# ARM_board.net
KiCad netlist of a schematic drawn in EAGLE
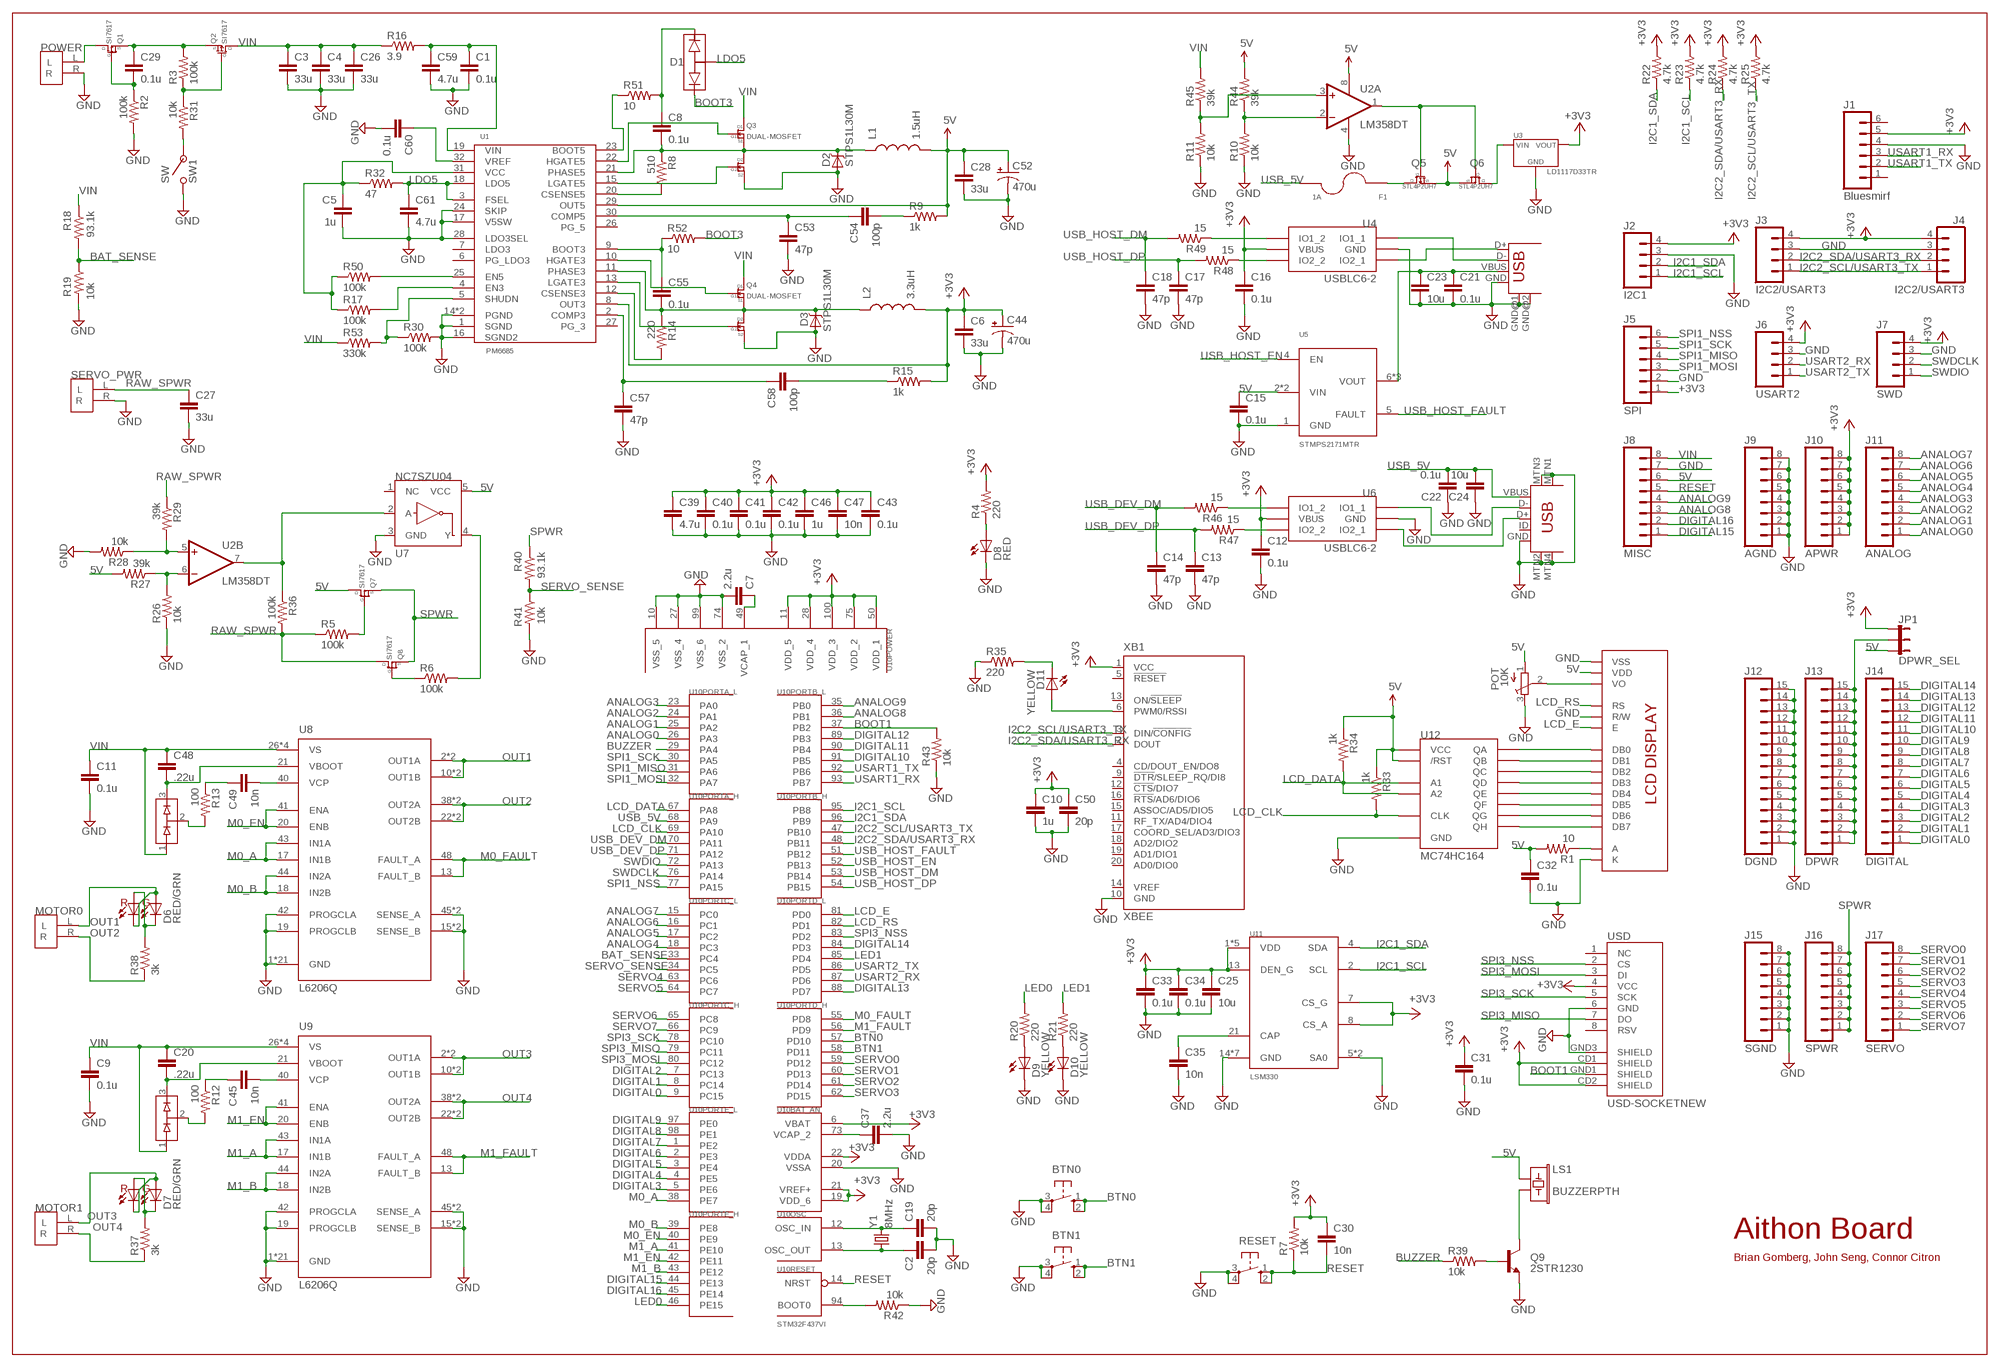
[diagram p0: schematic, sheet 1]

(export (version "E")
  (design (tool "Eeschema 10.0.6"))
  (components
    (comp (ref "BTN0")
      (value "10-XX")
      (footprint "eagle-import:B3F-10XX")
      (fields (field (name "MPN") "B3F-1000"))
      (libsource (lib "eagle-import") (part "10-XX"))
    )
    (comp (ref "BTN1")
      (value "10-XX")
      (footprint "eagle-import:B3F-10XX")
      (fields (field (name "MPN") "B3F-1000"))
      (libsource (lib "eagle-import") (part "10-XX"))
    )
    (comp (ref "C1")
      (value "0.1u")
      (footprint "eagle-import:0402-CAP")
      (libsource (lib "eagle-import") (part "CAP0402-CAP"))
    )
    (comp (ref "C2")
      (value "20p")
      (footprint "eagle-import:0402-CAP")
      (libsource (lib "eagle-import") (part "CAP0402-CAP"))
    )
    (comp (ref "C3")
      (value "33u")
      (footprint "eagle-import:1206")
      (libsource (lib "eagle-import") (part "CAP1206"))
    )
    (comp (ref "C4")
      (value "33u")
      (footprint "eagle-import:1206")
      (libsource (lib "eagle-import") (part "CAP1206"))
    )
    (comp (ref "C5")
      (value "1u")
      (footprint "eagle-import:0402-CAP")
      (libsource (lib "eagle-import") (part "CAP0402-CAP"))
    )
    (comp (ref "C6")
      (value "33u")
      (footprint "eagle-import:0805")
      (libsource (lib "eagle-import") (part "CAP0805"))
    )
    (comp (ref "C7")
      (value "2.2u")
      (footprint "eagle-import:0402-CAP")
      (libsource (lib "eagle-import") (part "CAP0402-CAP"))
    )
    (comp (ref "C8")
      (value "0.1u")
      (footprint "eagle-import:0402-CAP")
      (libsource (lib "eagle-import") (part "CAP0402-CAP"))
    )
    (comp (ref "C9")
      (value "0.1u")
      (footprint "eagle-import:0402-CAP")
      (libsource (lib "eagle-import") (part "CAP0402-CAP"))
    )
    (comp (ref "C10")
      (value "1u")
      (footprint "eagle-import:0402-CAP")
      (libsource (lib "eagle-import") (part "CAP0402-CAP"))
    )
    (comp (ref "C11")
      (value "0.1u")
      (footprint "eagle-import:0402-CAP")
      (libsource (lib "eagle-import") (part "CAP0402-CAP"))
    )
    (comp (ref "C12")
      (value "0.1u")
      (footprint "eagle-import:0402-CAP")
      (libsource (lib "eagle-import") (part "CAP0402-CAP"))
    )
    (comp (ref "C13")
      (value "47p")
      (footprint "eagle-import:0402-CAP")
      (libsource (lib "eagle-import") (part "CAP0402-CAP"))
    )
    (comp (ref "C14")
      (value "47p")
      (footprint "eagle-import:0402-CAP")
      (libsource (lib "eagle-import") (part "CAP0402-CAP"))
    )
    (comp (ref "C15")
      (value "0.1u")
      (footprint "eagle-import:0402-CAP")
      (libsource (lib "eagle-import") (part "CAP0402-CAP"))
    )
    (comp (ref "C16")
      (value "0.1u")
      (footprint "eagle-import:0402-CAP")
      (libsource (lib "eagle-import") (part "CAP0402-CAP"))
    )
    (comp (ref "C17")
      (value "47p")
      (footprint "eagle-import:0402-CAP")
      (libsource (lib "eagle-import") (part "CAP0402-CAP"))
    )
    (comp (ref "C18")
      (value "47p")
      (footprint "eagle-import:0402-CAP")
      (libsource (lib "eagle-import") (part "CAP0402-CAP"))
    )
    (comp (ref "C19")
      (value "20p")
      (footprint "eagle-import:0402-CAP")
      (libsource (lib "eagle-import") (part "CAP0402-CAP"))
    )
    (comp (ref "C20")
      (value ".22u")
      (footprint "eagle-import:0402-CAP")
      (libsource (lib "eagle-import") (part "CAP0402-CAP"))
    )
    (comp (ref "C21")
      (value "0.1u")
      (footprint "eagle-import:0402-CAP")
      (libsource (lib "eagle-import") (part "CAP0402-CAP"))
    )
    (comp (ref "C22")
      (value "0.1u")
      (footprint "eagle-import:0402-CAP")
      (libsource (lib "eagle-import") (part "CAP0402-CAP"))
    )
    (comp (ref "C23")
      (value "10u")
      (footprint "eagle-import:0603-CAP")
      (libsource (lib "eagle-import") (part "CAP0603-CAP"))
    )
    (comp (ref "C24")
      (value "10u")
      (footprint "eagle-import:0603-CAP")
      (libsource (lib "eagle-import") (part "CAP0603-CAP"))
    )
    (comp (ref "C25")
      (value "10u")
      (footprint "eagle-import:0603-CAP")
      (libsource (lib "eagle-import") (part "CAP0603-CAP"))
    )
    (comp (ref "C26")
      (value "33u")
      (footprint "eagle-import:1206")
      (libsource (lib "eagle-import") (part "CAP1206"))
    )
    (comp (ref "C27")
      (value "33u")
      (footprint "eagle-import:1206")
      (libsource (lib "eagle-import") (part "CAP1206"))
    )
    (comp (ref "C28")
      (value "33u")
      (footprint "eagle-import:0805")
      (libsource (lib "eagle-import") (part "CAP0805"))
    )
    (comp (ref "C29")
      (value "0.1u")
      (footprint "eagle-import:0402-CAP")
      (libsource (lib "eagle-import") (part "CAP0402-CAP"))
    )
    (comp (ref "C30")
      (value "10n")
      (footprint "eagle-import:0402-CAP")
      (libsource (lib "eagle-import") (part "CAP0402-CAP"))
    )
    (comp (ref "C31")
      (value "0.1u")
      (footprint "eagle-import:0402-CAP")
      (libsource (lib "eagle-import") (part "CAP0402-CAP"))
    )
    (comp (ref "C32")
      (value "0.1u")
      (footprint "eagle-import:0402-CAP")
      (libsource (lib "eagle-import") (part "CAP0402-CAP"))
    )
    (comp (ref "C33")
      (value "0.1u")
      (footprint "eagle-import:0402-CAP")
      (libsource (lib "eagle-import") (part "CAP0402-CAP"))
    )
    (comp (ref "C34")
      (value "0.1u")
      (footprint "eagle-import:0402-CAP")
      (libsource (lib "eagle-import") (part "CAP0402-CAP"))
    )
    (comp (ref "C35")
      (value "10n")
      (footprint "eagle-import:0402-CAP")
      (libsource (lib "eagle-import") (part "CAP0402-CAP"))
    )
    (comp (ref "C37")
      (value "2.2u")
      (footprint "eagle-import:0402-CAP")
      (libsource (lib "eagle-import") (part "CAP0402-CAP"))
    )
    (comp (ref "C39")
      (value "4.7u")
      (footprint "eagle-import:0603-CAP")
      (libsource (lib "eagle-import") (part "CAP0603-CAP"))
    )
    (comp (ref "C40")
      (value "0.1u")
      (footprint "eagle-import:0402-CAP")
      (libsource (lib "eagle-import") (part "CAP0402-CAP"))
    )
    (comp (ref "C41")
      (value "0.1u")
      (footprint "eagle-import:0402-CAP")
      (libsource (lib "eagle-import") (part "CAP0402-CAP"))
    )
    (comp (ref "C42")
      (value "0.1u")
      (footprint "eagle-import:0402-CAP")
      (libsource (lib "eagle-import") (part "CAP0402-CAP"))
    )
    (comp (ref "C43")
      (value "0.1u")
      (footprint "eagle-import:0402-CAP")
      (libsource (lib "eagle-import") (part "CAP0402-CAP"))
    )
    (comp (ref "C44")
      (value "470u")
      (footprint "eagle-import:PANASONIC_D")
      (libsource (lib "eagle-import") (part "CAP_POLD"))
    )
    (comp (ref "C45")
      (value "10n")
      (footprint "eagle-import:0402-CAP")
      (libsource (lib "eagle-import") (part "CAP0402-CAP"))
    )
    (comp (ref "C46")
      (value "1u")
      (footprint "eagle-import:0402-CAP")
      (libsource (lib "eagle-import") (part "CAP0402-CAP"))
    )
    (comp (ref "C47")
      (value "10n")
      (footprint "eagle-import:0402-CAP")
      (libsource (lib "eagle-import") (part "CAP0402-CAP"))
    )
    (comp (ref "C48")
      (value ".22u")
      (footprint "eagle-import:0402-CAP")
      (libsource (lib "eagle-import") (part "CAP0402-CAP"))
    )
    (comp (ref "C49")
      (value "10n")
      (footprint "eagle-import:0402-CAP")
      (libsource (lib "eagle-import") (part "CAP0402-CAP"))
    )
    (comp (ref "C50")
      (value "20p")
      (footprint "eagle-import:0402-CAP")
      (libsource (lib "eagle-import") (part "CAP0402-CAP"))
    )
    (comp (ref "C52")
      (value "470u")
      (footprint "eagle-import:PANASONIC_D")
      (libsource (lib "eagle-import") (part "CAP_POLD"))
    )
    (comp (ref "C53")
      (value "47p")
      (footprint "eagle-import:0402-CAP")
      (libsource (lib "eagle-import") (part "CAP0402-CAP"))
    )
    (comp (ref "C54")
      (value "100p")
      (footprint "eagle-import:0402-CAP")
      (libsource (lib "eagle-import") (part "CAP0402-CAP"))
    )
    (comp (ref "C55")
      (value "0.1u")
      (footprint "eagle-import:0402-CAP")
      (libsource (lib "eagle-import") (part "CAP0402-CAP"))
    )
    (comp (ref "C57")
      (value "47p")
      (footprint "eagle-import:0402-CAP")
      (libsource (lib "eagle-import") (part "CAP0402-CAP"))
    )
    (comp (ref "C58")
      (value "100p")
      (footprint "eagle-import:0402-CAP")
      (libsource (lib "eagle-import") (part "CAP0402-CAP"))
    )
    (comp (ref "C59")
      (value "4.7u")
      (footprint "eagle-import:0603-CAP")
      (libsource (lib "eagle-import") (part "CAP0603-CAP"))
    )
    (comp (ref "C60")
      (value "0.1u")
      (footprint "eagle-import:0402-CAP")
      (libsource (lib "eagle-import") (part "CAP0402-CAP"))
    )
    (comp (ref "C61")
      (value "4.7u")
      (footprint "eagle-import:0603-CAP")
      (libsource (lib "eagle-import") (part "CAP0603-CAP"))
    )
    (comp (ref "D1")
      (value "BAS70-06FILM")
      (footprint "eagle-import:SOT-23")
      (libsource (lib "eagle-import") (part "SOD-23"))
    )
    (comp (ref "D2")
      (value "STPS1L30M")
      (footprint "eagle-import:STPS1L30M")
      (libsource (lib "eagle-import") (part "DIODE-SCHOTTKYA"))
    )
    (comp (ref "D3")
      (value "STPS1L30M")
      (footprint "eagle-import:STPS1L30M")
      (libsource (lib "eagle-import") (part "DIODE-SCHOTTKYA"))
    )
    (comp (ref "D4")
      (value "BAS70-05FILM")
      (footprint "eagle-import:SOT-23")
      (libsource (lib "eagle-import") (part "BAV99"))
    )
    (comp (ref "D5")
      (value "BAV99")
      (footprint "eagle-import:SOT-23")
      (libsource (lib "eagle-import") (part "BAV99"))
    )
    (comp (ref "D6")
      (value "RED/GRN")
      (footprint "eagle-import:LED-0606")
      (libsource (lib "eagle-import") (part "LED_BICOLOR"))
    )
    (comp (ref "D7")
      (value "RED/GRN")
      (footprint "eagle-import:LED-0606")
      (libsource (lib "eagle-import") (part "LED_BICOLOR"))
    )
    (comp (ref "D8")
      (value "RED")
      (footprint "eagle-import:CHIP-LED0603")
      (libsource (lib "eagle-import") (part "LEDCHIP-LED0603"))
    )
    (comp (ref "D9")
      (value "YELLOW")
      (footprint "eagle-import:CHIP-LED0603")
      (libsource (lib "eagle-import") (part "LEDCHIP-LED0603"))
    )
    (comp (ref "D10")
      (value "YELLOW")
      (footprint "eagle-import:CHIP-LED0603")
      (libsource (lib "eagle-import") (part "LEDCHIP-LED0603"))
    )
    (comp (ref "D11")
      (value "YELLOW")
      (footprint "eagle-import:CHIP-LED0603")
      (libsource (lib "eagle-import") (part "LEDCHIP-LED0603"))
    )
    (comp (ref "F1")
      (value "1A")
      (footprint "eagle-import:1206")
      (libsource (lib "eagle-import") (part "POLYFUSE"))
    )
    (comp (ref "J1")
      (value "Bluesmirf")
      (footprint "eagle-import:1X06")
      (libsource (lib "eagle-import") (part "M06SIP"))
    )
    (comp (ref "J2")
      (value "I2C1")
      (footprint "eagle-import:1X04")
      (libsource (lib "eagle-import") (part "M04PTH"))
    )
    (comp (ref "J3")
      (value "I2C2/USART3")
      (footprint "eagle-import:1X04")
      (libsource (lib "eagle-import") (part "M04PTH"))
    )
    (comp (ref "J4")
      (value "I2C2/USART3")
      (footprint "eagle-import:1X04")
      (libsource (lib "eagle-import") (part "M04PTH"))
    )
    (comp (ref "J5")
      (value "SPI")
      (footprint "eagle-import:1X06")
      (libsource (lib "eagle-import") (part "M06SIP"))
    )
    (comp (ref "J6")
      (value "USART2")
      (footprint "eagle-import:1X04")
      (libsource (lib "eagle-import") (part "M04PTH"))
    )
    (comp (ref "J7")
      (value "SWD")
      (footprint "eagle-import:1X04")
      (libsource (lib "eagle-import") (part "M04PTH"))
    )
    (comp (ref "J8")
      (value "MISC")
      (footprint "eagle-import:1X08")
      (libsource (lib "eagle-import") (part "M081X08"))
    )
    (comp (ref "J9")
      (value "AGND")
      (footprint "eagle-import:1X08")
      (libsource (lib "eagle-import") (part "M081X08"))
    )
    (comp (ref "J10")
      (value "APWR")
      (footprint "eagle-import:1X08")
      (libsource (lib "eagle-import") (part "M081X08"))
    )
    (comp (ref "J11")
      (value "ANALOG")
      (footprint "eagle-import:1X08")
      (libsource (lib "eagle-import") (part "M081X08"))
    )
    (comp (ref "J12")
      (value "DGND")
      (footprint "eagle-import:1X15")
      (libsource (lib "eagle-import") (part "M15"))
    )
    (comp (ref "J13")
      (value "DPWR")
      (footprint "eagle-import:1X15")
      (libsource (lib "eagle-import") (part "M15"))
    )
    (comp (ref "J14")
      (value "DIGITAL")
      (footprint "eagle-import:1X15")
      (libsource (lib "eagle-import") (part "M15"))
    )
    (comp (ref "J15")
      (value "SGND")
      (footprint "eagle-import:1X08")
      (libsource (lib "eagle-import") (part "M081X08"))
    )
    (comp (ref "J16")
      (value "SPWR")
      (footprint "eagle-import:1X08")
      (libsource (lib "eagle-import") (part "M081X08"))
    )
    (comp (ref "J17")
      (value "SERVO")
      (footprint "eagle-import:1X08")
      (libsource (lib "eagle-import") (part "M081X08"))
    )
    (comp (ref "JP1")
      (value "DPWR_SEL")
      (footprint "eagle-import:1X03")
      (libsource (lib "eagle-import") (part "JUMPER-3PTH"))
    )
    (comp (ref "L1")
      (value "1.5uH")
      (footprint "eagle-import:INDUCTOR-LMIP707")
      (libsource (lib "eagle-import") (part "INDUCTOR2"))
    )
    (comp (ref "L2")
      (value "3.3uH")
      (footprint "eagle-import:INDUCTOR-0520CDMCDS")
      (libsource (lib "eagle-import") (part "INDUCTOR3"))
    )
    (comp (ref "LCD")
      (value "LCD_DISPLAY")
      (footprint "eagle-import:LCD")
      (libsource (lib "eagle-import") (part "LCD_DISPLAY"))
    )
    (comp (ref "LS1")
      (value "BUZZERPTH")
      (footprint "eagle-import:BUZZER-12MM")
      (libsource (lib "eagle-import") (part "BUZZERPTH"))
    )
    (comp (ref "MOTOR0")
      (value "2POS_TERMINAL")
      (footprint "eagle-import:2POS_TERMINAL")
      (libsource (lib "eagle-import") (part "2POS_TERMINAL"))
    )
    (comp (ref "MOTOR1")
      (value "2POS_TERMINAL")
      (footprint "eagle-import:2POS_TERMINAL")
      (libsource (lib "eagle-import") (part "2POS_TERMINAL"))
    )
    (comp (ref "POT")
      (value "10K")
      (footprint "eagle-import:POT")
      (libsource (lib "eagle-import") (part "POT"))
    )
    (comp (ref "POWER")
      (value "2POS_TERMINAL")
      (footprint "eagle-import:2POS_TERMINAL")
      (libsource (lib "eagle-import") (part "2POS_TERMINAL"))
    )
    (comp (ref "Q1")
      (value "SI7617")
      (footprint "eagle-import:POWERPAK1212-8")
      (libsource (lib "eagle-import") (part "SI7617"))
    )
    (comp (ref "Q2")
      (value "SI7617")
      (footprint "eagle-import:POWERPAK1212-8")
      (libsource (lib "eagle-import") (part "SI7617"))
    )
    (comp (ref "Q3")
      (value "DUAL-MOSFET")
      (footprint "eagle-import:DUAL-MOSFET-STL60N32N3LL")
      (libsource (lib "eagle-import") (part "DUAL-MOSFET"))
    )
    (comp (ref "Q4")
      (value "DUAL-MOSFET")
      (footprint "eagle-import:DUAL-MOSFET-STL60N32N3LL")
      (libsource (lib "eagle-import") (part "DUAL-MOSFET"))
    )
    (comp (ref "Q5")
      (value "STL4P2UH7")
      (footprint "eagle-import:POWERFLAT")
      (libsource (lib "eagle-import") (part "STL4P2UH7"))
    )
    (comp (ref "Q6")
      (value "STL4P2UH7")
      (footprint "eagle-import:POWERFLAT")
      (libsource (lib "eagle-import") (part "STL4P2UH7"))
    )
    (comp (ref "Q7")
      (value "SI7617")
      (footprint "eagle-import:POWERPAK1212-8")
      (libsource (lib "eagle-import") (part "SI7617"))
    )
    (comp (ref "Q8")
      (value "SI7617")
      (footprint "eagle-import:POWERPAK1212-8")
      (libsource (lib "eagle-import") (part "SI7617"))
    )
    (comp (ref "Q9")
      (value "2STR1230")
      (footprint "eagle-import:SOT23-3")
      (libsource (lib "eagle-import") (part "TRANSISTOR_NPNSOT23-3"))
    )
    (comp (ref "R1")
      (value "10")
      (footprint "eagle-import:0402-RES")
      (libsource (lib "eagle-import") (part "RESISTOR0402-RES"))
    )
    (comp (ref "R2")
      (value "100k")
      (footprint "eagle-import:0402-RES")
      (libsource (lib "eagle-import") (part "RESISTOR0402-RES"))
    )
    (comp (ref "R3")
      (value "100k")
      (footprint "eagle-import:0402-RES")
      (libsource (lib "eagle-import") (part "RESISTOR0402-RES"))
    )
    (comp (ref "R4")
      (value "220")
      (footprint "eagle-import:0402-RES")
      (libsource (lib "eagle-import") (part "RESISTOR0402-RES"))
    )
    (comp (ref "R5")
      (value "100k")
      (footprint "eagle-import:0402-RES")
      (libsource (lib "eagle-import") (part "RESISTOR0402-RES"))
    )
    (comp (ref "R6")
      (value "100k")
      (footprint "eagle-import:0402-RES")
      (libsource (lib "eagle-import") (part "RESISTOR0402-RES"))
    )
    (comp (ref "R7")
      (value "10k")
      (footprint "eagle-import:0402-RES")
      (libsource (lib "eagle-import") (part "RESISTOR0402-RES"))
    )
    (comp (ref "R8")
      (value "510")
      (footprint "eagle-import:0402-RES")
      (libsource (lib "eagle-import") (part "RESISTOR0402-RES"))
    )
    (comp (ref "R9")
      (value "1k")
      (footprint "eagle-import:0402-RES")
      (libsource (lib "eagle-import") (part "RESISTOR0402-RES"))
    )
    (comp (ref "R10")
      (value "10k")
      (footprint "eagle-import:0402-RES")
      (libsource (lib "eagle-import") (part "RESISTOR0402-RES"))
    )
    (comp (ref "R11")
      (value "10k")
      (footprint "eagle-import:0402-RES")
      (libsource (lib "eagle-import") (part "RESISTOR0402-RES"))
    )
    (comp (ref "R12")
      (value "100")
      (footprint "eagle-import:0402-RES")
      (libsource (lib "eagle-import") (part "RESISTOR0402-RES"))
    )
    (comp (ref "R13")
      (value "100")
      (footprint "eagle-import:0402-RES")
      (libsource (lib "eagle-import") (part "RESISTOR0402-RES"))
    )
    (comp (ref "R14")
      (value "220")
      (footprint "eagle-import:0402-RES")
      (libsource (lib "eagle-import") (part "RESISTOR0402-RES"))
    )
    (comp (ref "R15")
      (value "1k")
      (footprint "eagle-import:0402-RES")
      (libsource (lib "eagle-import") (part "RESISTOR0402-RES"))
    )
    (comp (ref "R16")
      (value "3.9")
      (footprint "eagle-import:0402-RES")
      (libsource (lib "eagle-import") (part "RESISTOR0402-RES"))
    )
    (comp (ref "R17")
      (value "100k")
      (footprint "eagle-import:0402-RES")
      (libsource (lib "eagle-import") (part "RESISTOR0402-RES"))
    )
    (comp (ref "R18")
      (value "93.1k")
      (footprint "eagle-import:0402-RES")
      (libsource (lib "eagle-import") (part "RESISTOR0402-RES"))
    )
    (comp (ref "R19")
      (value "10k")
      (footprint "eagle-import:0402-RES")
      (libsource (lib "eagle-import") (part "RESISTOR0402-RES"))
    )
    (comp (ref "R20")
      (value "220")
      (footprint "eagle-import:0402-RES")
      (libsource (lib "eagle-import") (part "RESISTOR0402-RES"))
    )
    (comp (ref "R21")
      (value "220")
      (footprint "eagle-import:0402-RES")
      (libsource (lib "eagle-import") (part "RESISTOR0402-RES"))
    )
    (comp (ref "R22")
      (value "4.7k")
      (footprint "eagle-import:0402-RES")
      (libsource (lib "eagle-import") (part "RESISTOR0402-RES"))
    )
    (comp (ref "R23")
      (value "4.7k")
      (footprint "eagle-import:0402-RES")
      (libsource (lib "eagle-import") (part "RESISTOR0402-RES"))
    )
    (comp (ref "R24")
      (value "4.7k")
      (footprint "eagle-import:0402-RES")
      (libsource (lib "eagle-import") (part "RESISTOR0402-RES"))
    )
    (comp (ref "R25")
      (value "4.7k")
      (footprint "eagle-import:0402-RES")
      (libsource (lib "eagle-import") (part "RESISTOR0402-RES"))
    )
    (comp (ref "R26")
      (value "10k")
      (footprint "eagle-import:0402-RES")
      (libsource (lib "eagle-import") (part "RESISTOR0402-RES"))
    )
    (comp (ref "R27")
      (value "39k")
      (footprint "eagle-import:0402-RES")
      (libsource (lib "eagle-import") (part "RESISTOR0402-RES"))
    )
    (comp (ref "R28")
      (value "10k")
      (footprint "eagle-import:0402-RES")
      (libsource (lib "eagle-import") (part "RESISTOR0402-RES"))
    )
    (comp (ref "R29")
      (value "39k")
      (footprint "eagle-import:0402-RES")
      (libsource (lib "eagle-import") (part "RESISTOR0402-RES"))
    )
    (comp (ref "R30")
      (value "100k")
      (footprint "eagle-import:0402-RES")
      (libsource (lib "eagle-import") (part "RESISTOR0402-RES"))
    )
    (comp (ref "R31")
      (value "10k")
      (footprint "eagle-import:0402-RES")
      (libsource (lib "eagle-import") (part "RESISTOR0402-RES"))
    )
    (comp (ref "R32")
      (value "47")
      (footprint "eagle-import:0402-RES")
      (libsource (lib "eagle-import") (part "RESISTOR0402-RES"))
    )
    (comp (ref "R33")
      (value "1k")
      (footprint "eagle-import:0402-RES")
      (libsource (lib "eagle-import") (part "RESISTOR0402-RES"))
    )
    (comp (ref "R34")
      (value "1k")
      (footprint "eagle-import:0402-RES")
      (libsource (lib "eagle-import") (part "RESISTOR0402-RES"))
    )
    (comp (ref "R35")
      (value "220")
      (footprint "eagle-import:0402-RES")
      (libsource (lib "eagle-import") (part "RESISTOR0402-RES"))
    )
    (comp (ref "R36")
      (value "100k")
      (footprint "eagle-import:0402-RES")
      (libsource (lib "eagle-import") (part "RESISTOR0402-RES"))
    )
    (comp (ref "R37")
      (value "3k")
      (footprint "eagle-import:0603-RES")
      (libsource (lib "eagle-import") (part "SparkFun-Resistors_RESISTOR0603-RES"))
    )
    (comp (ref "R38")
      (value "3k")
      (footprint "eagle-import:0603-RES")
      (libsource (lib "eagle-import") (part "SparkFun-Resistors_RESISTOR0603-RES"))
    )
    (comp (ref "R39")
      (value "10k")
      (footprint "eagle-import:0402-RES")
      (libsource (lib "eagle-import") (part "RESISTOR0402-RES"))
    )
    (comp (ref "R40")
      (value "93.1k")
      (footprint "eagle-import:0402-RES")
      (libsource (lib "eagle-import") (part "RESISTOR0402-RES"))
    )
    (comp (ref "R41")
      (value "10k")
      (footprint "eagle-import:0402-RES")
      (libsource (lib "eagle-import") (part "RESISTOR0402-RES"))
    )
    (comp (ref "R42")
      (value "10k")
      (footprint "eagle-import:0402-RES")
      (libsource (lib "eagle-import") (part "RESISTOR0402-RES"))
    )
    (comp (ref "R43")
      (value "10k")
      (footprint "eagle-import:0402-RES")
      (libsource (lib "eagle-import") (part "RESISTOR0402-RES"))
    )
    (comp (ref "R44")
      (value "39k")
      (footprint "eagle-import:0402-RES")
      (libsource (lib "eagle-import") (part "RESISTOR0402-RES"))
    )
    (comp (ref "R45")
      (value "39k")
      (footprint "eagle-import:0402-RES")
      (libsource (lib "eagle-import") (part "RESISTOR0402-RES"))
    )
    (comp (ref "R46")
      (value "15")
      (footprint "eagle-import:0402-RES")
      (libsource (lib "eagle-import") (part "RESISTOR0402-RES"))
    )
    (comp (ref "R47")
      (value "15")
      (footprint "eagle-import:0402-RES")
      (libsource (lib "eagle-import") (part "RESISTOR0402-RES"))
    )
    (comp (ref "R48")
      (value "15")
      (footprint "eagle-import:0402-RES")
      (libsource (lib "eagle-import") (part "RESISTOR0402-RES"))
    )
    (comp (ref "R49")
      (value "15")
      (footprint "eagle-import:0402-RES")
      (libsource (lib "eagle-import") (part "RESISTOR0402-RES"))
    )
    (comp (ref "R50")
      (value "100k")
      (footprint "eagle-import:0402-RES")
      (libsource (lib "eagle-import") (part "RESISTOR0402-RES"))
    )
    (comp (ref "R51")
      (value "10")
      (footprint "eagle-import:0402-RES")
      (libsource (lib "eagle-import") (part "RESISTOR0402-RES"))
    )
    (comp (ref "R52")
      (value "10")
      (footprint "eagle-import:0402-RES")
      (libsource (lib "eagle-import") (part "RESISTOR0402-RES"))
    )
    (comp (ref "R53")
      (value "330k")
      (footprint "eagle-import:0402-RES")
      (libsource (lib "eagle-import") (part "RESISTOR0402-RES"))
    )
    (comp (ref "RESET")
      (value "10-XX")
      (footprint "eagle-import:B3F-10XX")
      (fields (field (name "MPN") "B3F-1000"))
      (libsource (lib "eagle-import") (part "10-XX"))
    )
    (comp (ref "SERVO_PWR")
      (value "2POS_TERMINAL")
      (footprint "eagle-import:2POS_TERMINAL")
      (libsource (lib "eagle-import") (part "2POS_TERMINAL"))
    )
    (comp (ref "SW1") (value "SW") (footprint "eagle-import:SW") (libsource (lib "eagle-import") (part "SW")))
    (comp (ref "U1")
      (value "PM6685")
      (footprint "eagle-import:VFQFPN-32")
      (libsource (lib "eagle-import") (part "PM6685"))
    )
    (comp (ref "U2")
      (value "LM358DT")
      (footprint "eagle-import:SO08")
      (libsource (lib "eagle-import") (part "LM358D"))
    )
    (comp (ref "U3")
      (value "LD1117D33TR")
      (footprint "eagle-import:8-SOIC")
      (libsource (lib "eagle-import") (part "LD1117"))
    )
    (comp (ref "U4")
      (value "USBLC6-2")
      (footprint "eagle-import:SOT23-6L")
      (libsource (lib "eagle-import") (part "USBLC6-2"))
    )
    (comp (ref "U5")
      (value "STMPS2171MTR")
      (footprint "eagle-import:8-SOIC")
      (libsource (lib "eagle-import") (part "RT9715"))
    )
    (comp (ref "U6")
      (value "USBLC6-2")
      (footprint "eagle-import:SOT23-6L")
      (libsource (lib "eagle-import") (part "USBLC6-2"))
    )
    (comp (ref "U7")
      (value "NC7SZU04")
      (footprint "eagle-import:SC70")
      (libsource (lib "eagle-import") (part "INVERTER{dblquote}{dblquote}"))
    )
    (comp (ref "U8")
      (value "L6206Q")
      (footprint "eagle-import:VFQFPN48")
      (libsource (lib "eagle-import") (part "L6206Q"))
    )
    (comp (ref "U9")
      (value "L6206Q")
      (footprint "eagle-import:VFQFPN48")
      (libsource (lib "eagle-import") (part "L6206Q"))
    )
    (comp (ref "U10")
      (value "STM32F437VI")
      (footprint "eagle-import:TQFP100")
      (libsource (lib "eagle-import") (part "STM32F407VET"))
    )
    (comp (ref "U11")
      (value "LSM330")
      (footprint "eagle-import:LSM330")
      (libsource (lib "eagle-import") (part "LSM330"))
    )
    (comp (ref "U12")
      (value "MC74HC164")
      (footprint "eagle-import:TSSOP-14")
      (libsource (lib "eagle-import") (part "MC74HC164"))
    )
    (comp (ref "USB1")
      (value "USB-A-S")
      (footprint "eagle-import:USB-A-S")
      (libsource (lib "eagle-import") (part "USB-A-S"))
    )
    (comp (ref "USB2")
      (value "USB-MINIB-5PIN")
      (footprint "eagle-import:USB-MINIB")
      (libsource (lib "eagle-import") (part "USB-MINIB-5PIN"))
    )
    (comp (ref "USD")
      (value "USD-SOCKETNEW")
      (footprint "eagle-import:MICRO-SD-SOCKET-PP")
      (libsource (lib "eagle-import") (part "USD-SOCKETNEW"))
    )
    (comp (ref "XB1")
      (value "XBEE")
      (footprint "eagle-import:XBEE")
      (fields
        (field (name "MPN") "XBP24-Z7UIT-004")
        (field (name "MPN_1") "XBP24-Z7UIT-004")
        (field (name "OC_FARNELL") "1751799")
        (field (name "OC_NEWARK") "34R5507")
      )
      (libsource (lib "eagle-import") (part "XBEE"))
    )
    (comp (ref "Y1")
      (value "8MHz")
      (footprint "eagle-import:HC49UP")
      (libsource (lib "eagle-import") (part "CRYSTALSMD"))
    )
  )
  (nets
    (net (code "1") (name "+3V3") (class "Default")
      (node (ref "C10") (pin "1") (pinfunction "1_1") (pintype "passive"))
      (node (ref "C12") (pin "1") (pinfunction "1_1") (pintype "passive"))
      (node (ref "C16") (pin "1") (pinfunction "1_1") (pintype "passive"))
      (node (ref "C25") (pin "1") (pinfunction "1_1") (pintype "passive"))
      (node (ref "C30") (pin "1") (pinfunction "1_1") (pintype "passive"))
      (node (ref "C31") (pin "1") (pinfunction "1_1") (pintype "passive"))
      (node (ref "C33") (pin "1") (pinfunction "1_1") (pintype "passive"))
      (node (ref "C34") (pin "1") (pinfunction "1_1") (pintype "passive"))
      (node (ref "C39") (pin "1") (pinfunction "1_1") (pintype "passive"))
      (node (ref "C40") (pin "1") (pinfunction "1_1") (pintype "passive"))
      (node (ref "C41") (pin "1") (pinfunction "1_1") (pintype "passive"))
      (node (ref "C42") (pin "1") (pinfunction "1_1") (pintype "passive"))
      (node (ref "C43") (pin "1") (pinfunction "1_1") (pintype "passive"))
      (node (ref "C44") (pin "+") (pinfunction "+_+") (pintype "passive"))
      (node (ref "C46") (pin "1") (pinfunction "1_1") (pintype "passive"))
      (node (ref "C47") (pin "1") (pinfunction "1_1") (pintype "passive"))
      (node (ref "C50") (pin "1") (pinfunction "1_1") (pintype "passive"))
      (node (ref "C6") (pin "1") (pinfunction "1_1") (pintype "passive"))
      (node (ref "J1") (pin "5") (pinfunction "5_5") (pintype "passive"))
      (node (ref "J10") (pin "1") (pinfunction "1_1") (pintype "passive"))
      (node (ref "J10") (pin "2") (pinfunction "2_2") (pintype "passive"))
      (node (ref "J10") (pin "3") (pinfunction "3_3") (pintype "passive"))
      (node (ref "J10") (pin "4") (pinfunction "4_4") (pintype "passive"))
      (node (ref "J10") (pin "5") (pinfunction "5_5") (pintype "passive"))
      (node (ref "J10") (pin "6") (pinfunction "6_6") (pintype "passive"))
      (node (ref "J10") (pin "7") (pinfunction "7_7") (pintype "passive"))
      (node (ref "J10") (pin "8") (pinfunction "8_8") (pintype "passive"))
      (node (ref "J2") (pin "4") (pinfunction "4_4") (pintype "passive"))
      (node (ref "J3") (pin "4") (pinfunction "4_4") (pintype "passive"))
      (node (ref "J4") (pin "4") (pinfunction "4_4") (pintype "passive"))
      (node (ref "J5") (pin "1") (pinfunction "1_1") (pintype "passive"))
      (node (ref "J6") (pin "4") (pinfunction "4_4") (pintype "passive"))
      (node (ref "J7") (pin "4") (pinfunction "4_4") (pintype "passive"))
      (node (ref "JP1") (pin "1") (pinfunction "1_1") (pintype "passive"))
      (node (ref "L2") (pin "P$2") (pinfunction "2_P$2") (pintype "passive"))
      (node (ref "R15") (pin "2") (pinfunction "2_2") (pintype "passive"))
      (node (ref "R22") (pin "2") (pinfunction "2_2") (pintype "passive"))
      (node (ref "R23") (pin "2") (pinfunction "2_2") (pintype "passive"))
      (node (ref "R24") (pin "2") (pinfunction "2_2") (pintype "passive"))
      (node (ref "R25") (pin "2") (pinfunction "2_2") (pintype "passive"))
      (node (ref "R4") (pin "2") (pinfunction "2_2") (pintype "passive"))
      (node (ref "R7") (pin "2") (pinfunction "2_2") (pintype "passive"))
      (node (ref "U1") (pin "8") (pinfunction "OUT3_8") (pintype "bidirectional"))
      (node (ref "U10") (pin "100") (pinfunction "VDD_3_100") (pintype "power_in"))
      (node (ref "U10") (pin "11") (pinfunction "VDD_5_11") (pintype "power_in"))
      (node (ref "U10") (pin "19") (pinfunction "VDD_6_19") (pintype "input"))
      (node (ref "U10") (pin "21") (pinfunction "VREF+_21") (pintype "input"))
      (node (ref "U10") (pin "22") (pinfunction "VDDA_22") (pintype "power_in"))
      (node (ref "U10") (pin "28") (pinfunction "VDD_4_28") (pintype "power_in"))
      (node (ref "U10") (pin "50") (pinfunction "VDD_1_50") (pintype "power_in"))
      (node (ref "U10") (pin "6") (pinfunction "VBAT_6") (pintype "power_in"))
      (node (ref "U10") (pin "75") (pinfunction "VDD_2_75") (pintype "power_in"))
      (node (ref "U11") (pin "1") (pinfunction "VDD_1") (pintype "bidirectional"))
      (node (ref "U11") (pin "13") (pinfunction "DEN_G_13") (pintype "bidirectional"))
      (node (ref "U11") (pin "22") (pinfunction "VDD_22") (pintype "bidirectional"))
      (node (ref "U11") (pin "23") (pinfunction "VDD_23") (pintype "bidirectional"))
      (node (ref "U11") (pin "24") (pinfunction "VDD_24") (pintype "bidirectional"))
      (node (ref "U11") (pin "3") (pinfunction "VDD_3") (pintype "bidirectional"))
      (node (ref "U11") (pin "7") (pinfunction "CS_G_7") (pintype "bidirectional"))
      (node (ref "U11") (pin "8") (pinfunction "CS_A_8") (pintype "bidirectional"))
      (node (ref "U3") (pin "2") (pinfunction "VOUT_2") (pintype "bidirectional"))
      (node (ref "U3") (pin "3") (pinfunction "VOUT_3") (pintype "bidirectional"))
      (node (ref "U3") (pin "6") (pinfunction "VOUT_6") (pintype "bidirectional"))
      (node (ref "U3") (pin "7") (pinfunction "VOUT_7") (pintype "bidirectional"))
      (node (ref "U4") (pin "P$5") (pinfunction "VBUS_P$5") (pintype "bidirectional"))
      (node (ref "U6") (pin "P$5") (pinfunction "VBUS_P$5") (pintype "bidirectional"))
      (node (ref "USD") (pin "4") (pinfunction "VCC_4") (pintype "bidirectional"))
      (node (ref "USD") (pin "CD1") (pinfunction "SHIELD_CD1") (pintype "bidirectional"))
      (node (ref "USD") (pin "CD2") (pinfunction "SHIELD_CD2") (pintype "bidirectional"))
      (node (ref "XB1") (pin "1") (pinfunction "VCC_1") (pintype "power_in"))
    )
    (net (code "2") (name "/ANALOG0") (class "Default")
      (node (ref "J11") (pin "1") (pinfunction "1_1") (pintype "passive"))
      (node (ref "U10") (pin "26") (pinfunction "PA3_26") (pintype "bidirectional"))
    )
    (net (code "3") (name "/ANALOG1") (class "Default")
      (node (ref "J11") (pin "2") (pinfunction "2_2") (pintype "passive"))
      (node (ref "U10") (pin "25") (pinfunction "PA2_25") (pintype "bidirectional"))
    )
    (net (code "4") (name "/ANALOG2") (class "Default")
      (node (ref "J11") (pin "3") (pinfunction "3_3") (pintype "passive"))
      (node (ref "U10") (pin "24") (pinfunction "PA1_24") (pintype "bidirectional"))
    )
    (net (code "5") (name "/ANALOG3") (class "Default")
      (node (ref "J11") (pin "4") (pinfunction "4_4") (pintype "passive"))
      (node (ref "U10") (pin "23") (pinfunction "PA0_23") (pintype "bidirectional"))
    )
    (net (code "6") (name "/ANALOG4") (class "Default")
      (node (ref "J11") (pin "5") (pinfunction "5_5") (pintype "passive"))
      (node (ref "U10") (pin "18") (pinfunction "PC3_18") (pintype "bidirectional"))
    )
    (net (code "7") (name "/ANALOG5") (class "Default")
      (node (ref "J11") (pin "6") (pinfunction "6_6") (pintype "passive"))
      (node (ref "U10") (pin "17") (pinfunction "PC2_17") (pintype "bidirectional"))
    )
    (net (code "8") (name "/ANALOG6") (class "Default")
      (node (ref "J11") (pin "7") (pinfunction "7_7") (pintype "passive"))
      (node (ref "U10") (pin "16") (pinfunction "PC1_16") (pintype "bidirectional"))
    )
    (net (code "9") (name "/ANALOG7") (class "Default")
      (node (ref "J11") (pin "8") (pinfunction "8_8") (pintype "passive"))
      (node (ref "U10") (pin "15") (pinfunction "PC0_15") (pintype "bidirectional"))
    )
    (net (code "10") (name "/ANALOG8") (class "Default")
      (node (ref "J8") (pin "3") (pinfunction "3_3") (pintype "passive"))
      (node (ref "U10") (pin "36") (pinfunction "PB1_36") (pintype "bidirectional"))
    )
    (net (code "11") (name "/ANALOG9") (class "Default")
      (node (ref "J8") (pin "4") (pinfunction "4_4") (pintype "passive"))
      (node (ref "U10") (pin "35") (pinfunction "PB0_35") (pintype "bidirectional"))
    )
    (net (code "12") (name "/BAT_SENSE") (class "Default")
      (node (ref "R18") (pin "2") (pinfunction "2_2") (pintype "passive"))
      (node (ref "R19") (pin "1") (pinfunction "1_1") (pintype "passive"))
      (node (ref "U10") (pin "33") (pinfunction "PC4_33") (pintype "bidirectional"))
    )
    (net (code "13") (name "/BOOT1") (class "Default")
      (node (ref "R43") (pin "2") (pinfunction "2_2") (pintype "passive"))
      (node (ref "U10") (pin "37") (pinfunction "PB2_37") (pintype "bidirectional"))
      (node (ref "USD") (pin "GND1") (pinfunction "SHIELD_GND1") (pintype "bidirectional"))
    )
    (net (code "14") (name "/BOOT3") (class "Default")
      (node (ref "D1") (pin "P$2") (pinfunction "P$2_P$2") (pintype "output"))
      (node (ref "R52") (pin "2") (pinfunction "2_2") (pintype "passive"))
    )
    (net (code "15") (name "/BTN0") (class "Default")
      (node (ref "BTN0") (pin "1") (pinfunction "S_1") (pintype "passive"))
      (node (ref "BTN0") (pin "2") (pinfunction "S1_2") (pintype "passive"))
      (node (ref "U10") (pin "57") (pinfunction "PD10_57") (pintype "bidirectional"))
    )
    (net (code "16") (name "/BTN1") (class "Default")
      (node (ref "BTN1") (pin "1") (pinfunction "S_1") (pintype "passive"))
      (node (ref "BTN1") (pin "2") (pinfunction "S1_2") (pintype "passive"))
      (node (ref "U10") (pin "58") (pinfunction "PD11_58") (pintype "bidirectional"))
    )
    (net (code "17") (name "/BUZZER") (class "Default")
      (node (ref "R39") (pin "1") (pinfunction "1_1") (pintype "passive"))
      (node (ref "U10") (pin "29") (pinfunction "PA4_29") (pintype "bidirectional"))
    )
    (net (code "18") (name "/DIGITAL0") (class "Default")
      (node (ref "J14") (pin "1") (pinfunction "1_1") (pintype "passive"))
      (node (ref "U10") (pin "9") (pinfunction "PC15_9") (pintype "bidirectional"))
    )
    (net (code "19") (name "/DIGITAL1") (class "Default")
      (node (ref "J14") (pin "2") (pinfunction "2_2") (pintype "passive"))
      (node (ref "U10") (pin "8") (pinfunction "PC14_8") (pintype "bidirectional"))
    )
    (net (code "20") (name "/DIGITAL2") (class "Default")
      (node (ref "J14") (pin "3") (pinfunction "3_3") (pintype "passive"))
      (node (ref "U10") (pin "7") (pinfunction "PC13_7") (pintype "bidirectional"))
    )
    (net (code "21") (name "/DIGITAL3") (class "Default")
      (node (ref "J14") (pin "4") (pinfunction "4_4") (pintype "passive"))
      (node (ref "U10") (pin "5") (pinfunction "PE6_5") (pintype "bidirectional"))
    )
    (net (code "22") (name "/DIGITAL4") (class "Default")
      (node (ref "J14") (pin "5") (pinfunction "5_5") (pintype "passive"))
      (node (ref "U10") (pin "4") (pinfunction "PE5_4") (pintype "bidirectional"))
    )
    (net (code "23") (name "/DIGITAL5") (class "Default")
      (node (ref "J14") (pin "6") (pinfunction "6_6") (pintype "passive"))
      (node (ref "U10") (pin "3") (pinfunction "PE4_3") (pintype "bidirectional"))
    )
    (net (code "24") (name "/DIGITAL6") (class "Default")
      (node (ref "J14") (pin "7") (pinfunction "7_7") (pintype "passive"))
      (node (ref "U10") (pin "2") (pinfunction "PE3_2") (pintype "bidirectional"))
    )
    (net (code "25") (name "/DIGITAL7") (class "Default")
      (node (ref "J14") (pin "8") (pinfunction "8_8") (pintype "passive"))
      (node (ref "U10") (pin "1") (pinfunction "PE2_1") (pintype "bidirectional"))
    )
    (net (code "26") (name "/DIGITAL8") (class "Default")
      (node (ref "J14") (pin "9") (pinfunction "9_9") (pintype "passive"))
      (node (ref "U10") (pin "98") (pinfunction "PE1_98") (pintype "bidirectional"))
    )
    (net (code "27") (name "/DIGITAL9") (class "Default")
      (node (ref "J14") (pin "10") (pinfunction "10_10") (pintype "passive"))
      (node (ref "U10") (pin "97") (pinfunction "PE0_97") (pintype "bidirectional"))
    )
    (net (code "28") (name "/DIGITAL10") (class "Default")
      (node (ref "J14") (pin "11") (pinfunction "11_11") (pintype "passive"))
      (node (ref "U10") (pin "91") (pinfunction "PB5_91") (pintype "bidirectional"))
    )
    (net (code "29") (name "/DIGITAL11") (class "Default")
      (node (ref "J14") (pin "12") (pinfunction "12_12") (pintype "passive"))
      (node (ref "U10") (pin "90") (pinfunction "PB4_90") (pintype "bidirectional"))
    )
    (net (code "30") (name "/DIGITAL12") (class "Default")
      (node (ref "J14") (pin "13") (pinfunction "13_13") (pintype "passive"))
      (node (ref "U10") (pin "89") (pinfunction "PB3_89") (pintype "bidirectional"))
    )
    (net (code "31") (name "/DIGITAL13") (class "Default")
      (node (ref "J14") (pin "14") (pinfunction "14_14") (pintype "passive"))
      (node (ref "U10") (pin "88") (pinfunction "PD7_88") (pintype "bidirectional"))
    )
    (net (code "32") (name "/DIGITAL14") (class "Default")
      (node (ref "J14") (pin "15") (pinfunction "15_15") (pintype "passive"))
      (node (ref "U10") (pin "84") (pinfunction "PD3_84") (pintype "bidirectional"))
    )
    (net (code "33") (name "/DIGITAL15") (class "Default")
      (node (ref "J8") (pin "1") (pinfunction "1_1") (pintype "passive"))
      (node (ref "U10") (pin "44") (pinfunction "PE13_44") (pintype "bidirectional"))
    )
    (net (code "34") (name "/DIGITAL16") (class "Default")
      (node (ref "J8") (pin "2") (pinfunction "2_2") (pintype "passive"))
      (node (ref "U10") (pin "45") (pinfunction "PE14_45") (pintype "bidirectional"))
    )
    (net (code "35") (name "/I2C1_SCL") (class "Default")
      (node (ref "J2") (pin "1") (pinfunction "1_1") (pintype "passive"))
      (node (ref "R23") (pin "1") (pinfunction "1_1") (pintype "passive"))
      (node (ref "U10") (pin "95") (pinfunction "PB8_95") (pintype "bidirectional"))
      (node (ref "U11") (pin "2") (pinfunction "SCL_2") (pintype "bidirectional"))
    )
    (net (code "36") (name "/I2C1_SDA") (class "Default")
      (node (ref "J2") (pin "2") (pinfunction "2_2") (pintype "passive"))
      (node (ref "R22") (pin "1") (pinfunction "1_1") (pintype "passive"))
      (node (ref "U10") (pin "96") (pinfunction "PB9_96") (pintype "bidirectional"))
      (node (ref "U11") (pin "4") (pinfunction "SDA_4") (pintype "bidirectional"))
    )
    (net (code "37") (name "/I2C2_SCL{slash}USART3_TX") (class "Default")
      (node (ref "J3") (pin "1") (pinfunction "1_1") (pintype "passive"))
      (node (ref "J4") (pin "1") (pinfunction "1_1") (pintype "passive"))
      (node (ref "R25") (pin "1") (pinfunction "1_1") (pintype "passive"))
      (node (ref "U10") (pin "47") (pinfunction "PB10_47") (pintype "bidirectional"))
      (node (ref "XB1") (pin "3") (pinfunction "DIN/~{CONFIG}_3") (pintype "input"))
    )
    (net (code "38") (name "/I2C2_SDA{slash}USART3_RX") (class "Default")
      (node (ref "J3") (pin "2") (pinfunction "2_2") (pintype "passive"))
      (node (ref "J4") (pin "2") (pinfunction "2_2") (pintype "passive"))
      (node (ref "R24") (pin "1") (pinfunction "1_1") (pintype "passive"))
      (node (ref "U10") (pin "48") (pinfunction "PB11_48") (pintype "bidirectional"))
      (node (ref "XB1") (pin "2") (pinfunction "DOUT_2") (pintype "output"))
    )
    (net (code "39") (name "/LCD_CLK") (class "Default")
      (node (ref "R33") (pin "2") (pinfunction "2_2") (pintype "passive"))
      (node (ref "U10") (pin "69") (pinfunction "PA10_69") (pintype "bidirectional"))
      (node (ref "U12") (pin "8") (pinfunction "CLK_8") (pintype "bidirectional"))
    )
    (net (code "40") (name "/LCD_DATA") (class "Default")
      (node (ref "R34") (pin "2") (pinfunction "2_2") (pintype "passive"))
      (node (ref "U10") (pin "67") (pinfunction "PA8_67") (pintype "bidirectional"))
      (node (ref "U12") (pin "1") (pinfunction "A1_1") (pintype "bidirectional"))
      (node (ref "U12") (pin "2") (pinfunction "A2_2") (pintype "bidirectional"))
    )
    (net (code "41") (name "/LCD_E") (class "Default")
      (node (ref "LCD") (pin "E") (pinfunction "E_E") (pintype "bidirectional"))
      (node (ref "U10") (pin "81") (pinfunction "PD0_81") (pintype "bidirectional"))
    )
    (net (code "42") (name "/LCD_RS") (class "Default")
      (node (ref "LCD") (pin "RS") (pinfunction "RS_RS") (pintype "bidirectional"))
      (node (ref "U10") (pin "82") (pinfunction "PD1_82") (pintype "bidirectional"))
    )
    (net (code "43") (name "/LDO5") (class "Default")
      (node (ref "C61") (pin "1") (pinfunction "1_1") (pintype "passive"))
      (node (ref "D1") (pin "P$0") (pinfunction "P$0_P$0") (pintype "input"))
      (node (ref "R32") (pin "2") (pinfunction "2_2") (pintype "passive"))
      (node (ref "U1") (pin "18") (pinfunction "LDO5_18") (pintype "bidirectional"))
      (node (ref "U1") (pin "3") (pinfunction "FSEL_3") (pintype "bidirectional"))
    )
    (net (code "44") (name "/LED0") (class "Default")
      (node (ref "R20") (pin "2") (pinfunction "2_2") (pintype "passive"))
      (node (ref "U10") (pin "46") (pinfunction "PE15_46") (pintype "bidirectional"))
    )
    (net (code "45") (name "/LED1") (class "Default")
      (node (ref "R21") (pin "2") (pinfunction "2_2") (pintype "passive"))
      (node (ref "U10") (pin "85") (pinfunction "PD4_85") (pintype "bidirectional"))
    )
    (net (code "46") (name "/M0_A") (class "Default")
      (node (ref "U10") (pin "38") (pinfunction "PE7_38") (pintype "bidirectional"))
      (node (ref "U8") (pin "17") (pinfunction "IN1B_17") (pintype "bidirectional"))
      (node (ref "U8") (pin "43") (pinfunction "IN1A_43") (pintype "bidirectional"))
    )
    (net (code "47") (name "/M0_B") (class "Default")
      (node (ref "U10") (pin "39") (pinfunction "PE8_39") (pintype "bidirectional"))
      (node (ref "U8") (pin "18") (pinfunction "IN2B_18") (pintype "bidirectional"))
      (node (ref "U8") (pin "44") (pinfunction "IN2A_44") (pintype "bidirectional"))
    )
    (net (code "48") (name "/M0_EN") (class "Default")
      (node (ref "U10") (pin "40") (pinfunction "PE9_40") (pintype "bidirectional"))
      (node (ref "U8") (pin "20") (pinfunction "ENB_20") (pintype "bidirectional"))
      (node (ref "U8") (pin "41") (pinfunction "ENA_41") (pintype "bidirectional"))
    )
    (net (code "49") (name "/M0_FAULT") (class "Default")
      (node (ref "U10") (pin "55") (pinfunction "PD8_55") (pintype "bidirectional"))
      (node (ref "U8") (pin "13") (pinfunction "FAULT_B_13") (pintype "bidirectional"))
      (node (ref "U8") (pin "48") (pinfunction "FAULT_A_48") (pintype "bidirectional"))
    )
    (net (code "50") (name "/M1_A") (class "Default")
      (node (ref "U10") (pin "41") (pinfunction "PE10_41") (pintype "bidirectional"))
      (node (ref "U9") (pin "17") (pinfunction "IN1B_17") (pintype "bidirectional"))
      (node (ref "U9") (pin "43") (pinfunction "IN1A_43") (pintype "bidirectional"))
    )
    (net (code "51") (name "/M1_B") (class "Default")
      (node (ref "U10") (pin "43") (pinfunction "PE12_43") (pintype "bidirectional"))
      (node (ref "U9") (pin "18") (pinfunction "IN2B_18") (pintype "bidirectional"))
      (node (ref "U9") (pin "44") (pinfunction "IN2A_44") (pintype "bidirectional"))
    )
    (net (code "52") (name "/M1_EN") (class "Default")
      (node (ref "U10") (pin "42") (pinfunction "PE11_42") (pintype "bidirectional"))
      (node (ref "U9") (pin "20") (pinfunction "ENB_20") (pintype "bidirectional"))
      (node (ref "U9") (pin "41") (pinfunction "ENA_41") (pintype "bidirectional"))
    )
    (net (code "53") (name "/M1_FAULT") (class "Default")
      (node (ref "U10") (pin "56") (pinfunction "PD9_56") (pintype "bidirectional"))
      (node (ref "U9") (pin "13") (pinfunction "FAULT_B_13") (pintype "bidirectional"))
      (node (ref "U9") (pin "48") (pinfunction "FAULT_A_48") (pintype "bidirectional"))
    )
    (net (code "54") (name "/OUT1") (class "Default")
      (node (ref "D6") (pin "2") (pinfunction "2_2") (pintype "passive"))
      (node (ref "D6") (pin "3") (pinfunction "3_3") (pintype "passive"))
      (node (ref "MOTOR0") (pin "L") (pinfunction "L_L") (pintype "bidirectional"))
      (node (ref "U8") (pin "10") (pinfunction "OUT1B_10") (pintype "bidirectional"))
      (node (ref "U8") (pin "11") (pinfunction "OUT1B_11") (pintype "bidirectional"))
      (node (ref "U8") (pin "2") (pinfunction "OUT1A_2") (pintype "bidirectional"))
      (node (ref "U8") (pin "3") (pinfunction "OUT1A_3") (pintype "bidirectional"))
    )
    (net (code "55") (name "/OUT2") (class "Default")
      (node (ref "MOTOR0") (pin "R") (pinfunction "R_R") (pintype "bidirectional"))
      (node (ref "R38") (pin "1") (pinfunction "1_1") (pintype "passive"))
      (node (ref "U8") (pin "22") (pinfunction "OUT2B_22") (pintype "bidirectional"))
      (node (ref "U8") (pin "23") (pinfunction "OUT2B_23") (pintype "bidirectional"))
      (node (ref "U8") (pin "38") (pinfunction "OUT2A_38") (pintype "bidirectional"))
      (node (ref "U8") (pin "39") (pinfunction "OUT2A_39") (pintype "bidirectional"))
    )
    (net (code "56") (name "/OUT3") (class "Default")
      (node (ref "D7") (pin "2") (pinfunction "2_2") (pintype "passive"))
      (node (ref "D7") (pin "3") (pinfunction "3_3") (pintype "passive"))
      (node (ref "MOTOR1") (pin "L") (pinfunction "L_L") (pintype "bidirectional"))
      (node (ref "U9") (pin "10") (pinfunction "OUT1B_10") (pintype "bidirectional"))
      (node (ref "U9") (pin "11") (pinfunction "OUT1B_11") (pintype "bidirectional"))
      (node (ref "U9") (pin "2") (pinfunction "OUT1A_2") (pintype "bidirectional"))
      (node (ref "U9") (pin "3") (pinfunction "OUT1A_3") (pintype "bidirectional"))
    )
    (net (code "57") (name "/OUT4") (class "Default")
      (node (ref "MOTOR1") (pin "R") (pinfunction "R_R") (pintype "bidirectional"))
      (node (ref "R37") (pin "1") (pinfunction "1_1") (pintype "passive"))
      (node (ref "U9") (pin "22") (pinfunction "OUT2B_22") (pintype "bidirectional"))
      (node (ref "U9") (pin "23") (pinfunction "OUT2B_23") (pintype "bidirectional"))
      (node (ref "U9") (pin "38") (pinfunction "OUT2A_38") (pintype "bidirectional"))
      (node (ref "U9") (pin "39") (pinfunction "OUT2A_39") (pintype "bidirectional"))
    )
    (net (code "58") (name "/RAW_SPWR") (class "Default")
      (node (ref "C27") (pin "1") (pinfunction "1_1") (pintype "passive"))
      (node (ref "Q8") (pin "5") (pinfunction "D_5") (pintype "bidirectional"))
      (node (ref "Q8") (pin "6") (pinfunction "D_6") (pintype "bidirectional"))
      (node (ref "Q8") (pin "7") (pinfunction "D_7") (pintype "bidirectional"))
      (node (ref "Q8") (pin "8") (pinfunction "D_8") (pintype "bidirectional"))
      (node (ref "Q8") (pin "PAD") (pinfunction "D_PAD") (pintype "bidirectional"))
      (node (ref "R29") (pin "1") (pinfunction "1_1") (pintype "passive"))
      (node (ref "R36") (pin "2") (pinfunction "2_2") (pintype "passive"))
      (node (ref "R5") (pin "1") (pinfunction "1_1") (pintype "passive"))
      (node (ref "SERVO_PWR") (pin "L") (pinfunction "L_L") (pintype "bidirectional"))
    )
    (net (code "59") (name "/RESET") (class "Default")
      (node (ref "C30") (pin "2") (pinfunction "2_2") (pintype "passive"))
      (node (ref "J8") (pin "5") (pinfunction "5_5") (pintype "passive"))
      (node (ref "R7") (pin "1") (pinfunction "1_1") (pintype "passive"))
      (node (ref "RESET") (pin "1") (pinfunction "S_1") (pintype "passive"))
      (node (ref "RESET") (pin "2") (pinfunction "S1_2") (pintype "passive"))
      (node (ref "U10") (pin "14") (pinfunction "NRST_14") (pintype "input"))
    )
    (net (code "60") (name "/SERVO0") (class "Default")
      (node (ref "J17") (pin "8") (pinfunction "8_8") (pintype "passive"))
      (node (ref "U10") (pin "59") (pinfunction "PD12_59") (pintype "bidirectional"))
    )
    (net (code "61") (name "/SERVO1") (class "Default")
      (node (ref "J17") (pin "7") (pinfunction "7_7") (pintype "passive"))
      (node (ref "U10") (pin "60") (pinfunction "PD13_60") (pintype "bidirectional"))
    )
    (net (code "62") (name "/SERVO2") (class "Default")
      (node (ref "J17") (pin "6") (pinfunction "6_6") (pintype "passive"))
      (node (ref "U10") (pin "61") (pinfunction "PD14_61") (pintype "bidirectional"))
    )
    (net (code "63") (name "/SERVO3") (class "Default")
      (node (ref "J17") (pin "5") (pinfunction "5_5") (pintype "passive"))
      (node (ref "U10") (pin "62") (pinfunction "PD15_62") (pintype "bidirectional"))
    )
    (net (code "64") (name "/SERVO4") (class "Default")
      (node (ref "J17") (pin "4") (pinfunction "4_4") (pintype "passive"))
      (node (ref "U10") (pin "63") (pinfunction "PC6_63") (pintype "bidirectional"))
    )
    (net (code "65") (name "/SERVO5") (class "Default")
      (node (ref "J17") (pin "3") (pinfunction "3_3") (pintype "passive"))
      (node (ref "U10") (pin "64") (pinfunction "PC7_64") (pintype "bidirectional"))
    )
    (net (code "66") (name "/SERVO6") (class "Default")
      (node (ref "J17") (pin "2") (pinfunction "2_2") (pintype "passive"))
      (node (ref "U10") (pin "65") (pinfunction "PC8_65") (pintype "bidirectional"))
    )
    (net (code "67") (name "/SERVO7") (class "Default")
      (node (ref "J17") (pin "1") (pinfunction "1_1") (pintype "passive"))
      (node (ref "U10") (pin "66") (pinfunction "PC9_66") (pintype "bidirectional"))
    )
    (net (code "68") (name "/SERVO_SENSE") (class "Default")
      (node (ref "R40") (pin "2") (pinfunction "2_2") (pintype "passive"))
      (node (ref "R41") (pin "1") (pinfunction "1_1") (pintype "passive"))
      (node (ref "U10") (pin "34") (pinfunction "PC5_34") (pintype "bidirectional"))
    )
    (net (code "69") (name "/SPI1_MISO") (class "Default")
      (node (ref "J5") (pin "4") (pinfunction "4_4") (pintype "passive"))
      (node (ref "U10") (pin "31") (pinfunction "PA6_31") (pintype "bidirectional"))
    )
    (net (code "70") (name "/SPI1_MOSI") (class "Default")
      (node (ref "J5") (pin "3") (pinfunction "3_3") (pintype "passive"))
      (node (ref "U10") (pin "32") (pinfunction "PA7_32") (pintype "bidirectional"))
    )
    (net (code "71") (name "/SPI1_NSS") (class "Default")
      (node (ref "J5") (pin "6") (pinfunction "6_6") (pintype "passive"))
      (node (ref "U10") (pin "77") (pinfunction "PA15_77") (pintype "bidirectional"))
    )
    (net (code "72") (name "/SPI1_SCK") (class "Default")
      (node (ref "J5") (pin "5") (pinfunction "5_5") (pintype "passive"))
      (node (ref "U10") (pin "30") (pinfunction "PA5_30") (pintype "bidirectional"))
    )
    (net (code "73") (name "/SPI3_MISO") (class "Default")
      (node (ref "U10") (pin "79") (pinfunction "PC11_79") (pintype "bidirectional"))
      (node (ref "USD") (pin "7") (pinfunction "DO_7") (pintype "bidirectional"))
    )
    (net (code "74") (name "/SPI3_MOSI") (class "Default")
      (node (ref "U10") (pin "80") (pinfunction "PC12_80") (pintype "bidirectional"))
      (node (ref "USD") (pin "3") (pinfunction "DI_3") (pintype "bidirectional"))
    )
    (net (code "75") (name "/SPI3_NSS") (class "Default")
      (node (ref "U10") (pin "83") (pinfunction "PD2_83") (pintype "bidirectional"))
      (node (ref "USD") (pin "2") (pinfunction "CS_2") (pintype "bidirectional"))
    )
    (net (code "76") (name "/SPI3_SCK") (class "Default")
      (node (ref "U10") (pin "78") (pinfunction "PC10_78") (pintype "bidirectional"))
      (node (ref "USD") (pin "5") (pinfunction "SCK_5") (pintype "bidirectional"))
    )
    (net (code "77") (name "/SPWR") (class "Default")
      (node (ref "J16") (pin "1") (pinfunction "1_1") (pintype "passive"))
      (node (ref "J16") (pin "2") (pinfunction "2_2") (pintype "passive"))
      (node (ref "J16") (pin "3") (pinfunction "3_3") (pintype "passive"))
      (node (ref "J16") (pin "4") (pinfunction "4_4") (pintype "passive"))
      (node (ref "J16") (pin "5") (pinfunction "5_5") (pintype "passive"))
      (node (ref "J16") (pin "6") (pinfunction "6_6") (pintype "passive"))
      (node (ref "J16") (pin "7") (pinfunction "7_7") (pintype "passive"))
      (node (ref "J16") (pin "8") (pinfunction "8_8") (pintype "passive"))
      (node (ref "Q7") (pin "1") (pinfunction "S_1") (pintype "bidirectional"))
      (node (ref "Q7") (pin "2") (pinfunction "S_2") (pintype "bidirectional"))
      (node (ref "Q7") (pin "3") (pinfunction "S_3") (pintype "bidirectional"))
      (node (ref "Q8") (pin "1") (pinfunction "S_1") (pintype "bidirectional"))
      (node (ref "Q8") (pin "2") (pinfunction "S_2") (pintype "bidirectional"))
      (node (ref "Q8") (pin "3") (pinfunction "S_3") (pintype "bidirectional"))
      (node (ref "R40") (pin "1") (pinfunction "1_1") (pintype "passive"))
    )
    (net (code "78") (name "/SWDCLK") (class "Default")
      (node (ref "J7") (pin "2") (pinfunction "2_2") (pintype "passive"))
      (node (ref "U10") (pin "76") (pinfunction "PA14_76") (pintype "bidirectional"))
    )
    (net (code "79") (name "/SWDIO") (class "Default")
      (node (ref "J7") (pin "1") (pinfunction "1_1") (pintype "passive"))
      (node (ref "U10") (pin "72") (pinfunction "PA13_72") (pintype "bidirectional"))
    )
    (net (code "80") (name "/USART1_RX") (class "Default")
      (node (ref "J1") (pin "3") (pinfunction "3_3") (pintype "passive"))
      (node (ref "U10") (pin "93") (pinfunction "PB7_93") (pintype "bidirectional"))
    )
    (net (code "81") (name "/USART1_TX") (class "Default")
      (node (ref "J1") (pin "2") (pinfunction "2_2") (pintype "passive"))
      (node (ref "U10") (pin "92") (pinfunction "PB6_92") (pintype "bidirectional"))
    )
    (net (code "82") (name "/USART2_RX") (class "Default")
      (node (ref "J6") (pin "2") (pinfunction "2_2") (pintype "passive"))
      (node (ref "U10") (pin "87") (pinfunction "PD6_87") (pintype "bidirectional"))
    )
    (net (code "83") (name "/USART2_TX") (class "Default")
      (node (ref "J6") (pin "1") (pinfunction "1_1") (pintype "passive"))
      (node (ref "U10") (pin "86") (pinfunction "PD5_86") (pintype "bidirectional"))
    )
    (net (code "84") (name "/USB_5V") (class "Default")
      (node (ref "C22") (pin "2") (pinfunction "2_2") (pintype "passive"))
      (node (ref "C24") (pin "2") (pinfunction "2_2") (pintype "passive"))
      (node (ref "F1") (pin "2") (pinfunction "2_2") (pintype "bidirectional"))
      (node (ref "U10") (pin "68") (pinfunction "PA9_68") (pintype "bidirectional"))
      (node (ref "USB2") (pin "VBUS") (pinfunction "VBUS_VBUS") (pintype "bidirectional"))
    )
    (net (code "85") (name "/USB_DEV_DM") (class "Default")
      (node (ref "C14") (pin "1") (pinfunction "1_1") (pintype "passive"))
      (node (ref "R46") (pin "2") (pinfunction "2_2") (pintype "passive"))
      (node (ref "U10") (pin "70") (pinfunction "PA11_70") (pintype "bidirectional"))
    )
    (net (code "86") (name "/USB_DEV_DP") (class "Default")
      (node (ref "C13") (pin "1") (pinfunction "1_1") (pintype "passive"))
      (node (ref "R47") (pin "2") (pinfunction "2_2") (pintype "passive"))
      (node (ref "U10") (pin "71") (pinfunction "PA12_71") (pintype "bidirectional"))
    )
    (net (code "87") (name "/USB_HOST_DM") (class "Default")
      (node (ref "C18") (pin "1") (pinfunction "1_1") (pintype "passive"))
      (node (ref "R49") (pin "2") (pinfunction "2_2") (pintype "passive"))
      (node (ref "U10") (pin "53") (pinfunction "PB14_53") (pintype "bidirectional"))
    )
    (net (code "88") (name "/USB_HOST_DP") (class "Default")
      (node (ref "C17") (pin "1") (pinfunction "1_1") (pintype "passive"))
      (node (ref "R48") (pin "2") (pinfunction "2_2") (pintype "passive"))
      (node (ref "U10") (pin "54") (pinfunction "PB15_54") (pintype "bidirectional"))
    )
    (net (code "89") (name "/USB_HOST_EN") (class "Default")
      (node (ref "U10") (pin "52") (pinfunction "PB13_52") (pintype "bidirectional"))
      (node (ref "U5") (pin "4") (pinfunction "EN_4") (pintype "bidirectional"))
    )
    (net (code "90") (name "/USB_HOST_FAULT") (class "Default")
      (node (ref "U10") (pin "51") (pinfunction "PB12_51") (pintype "bidirectional"))
      (node (ref "U5") (pin "5") (pinfunction "FAULT_5") (pintype "bidirectional"))
    )
    (net (code "91") (name "/VIN") (class "Default")
      (node (ref "C11") (pin "1") (pinfunction "1_1") (pintype "passive"))
      (node (ref "C20") (pin "1") (pinfunction "1_1") (pintype "passive"))
      (node (ref "C26") (pin "1") (pinfunction "1_1") (pintype "passive"))
      (node (ref "C3") (pin "1") (pinfunction "1_1") (pintype "passive"))
      (node (ref "C4") (pin "1") (pinfunction "1_1") (pintype "passive"))
      (node (ref "C48") (pin "1") (pinfunction "1_1") (pintype "passive"))
      (node (ref "C9") (pin "1") (pinfunction "1_1") (pintype "passive"))
      (node (ref "D4") (pin "1") (pinfunction "1_1") (pintype "bidirectional"))
      (node (ref "D5") (pin "1") (pinfunction "1_1") (pintype "bidirectional"))
      (node (ref "J8") (pin "8") (pinfunction "8_8") (pintype "passive"))
      (node (ref "Q2") (pin "5") (pinfunction "D_5") (pintype "bidirectional"))
      (node (ref "Q2") (pin "6") (pinfunction "D_6") (pintype "bidirectional"))
      (node (ref "Q2") (pin "7") (pinfunction "D_7") (pintype "bidirectional"))
      (node (ref "Q2") (pin "8") (pinfunction "D_8") (pintype "bidirectional"))
      (node (ref "Q2") (pin "PAD") (pinfunction "D_PAD") (pintype "bidirectional"))
      (node (ref "Q3") (pin "2/3/4") (pinfunction "D1_2/3/4") (pintype "bidirectional"))
      (node (ref "Q3") (pin "D1") (pinfunction "D1_D1") (pintype "bidirectional"))
      (node (ref "Q4") (pin "2/3/4") (pinfunction "D1_2/3/4") (pintype "bidirectional"))
      (node (ref "Q4") (pin "D1") (pinfunction "D1_D1") (pintype "bidirectional"))
      (node (ref "R16") (pin "1") (pinfunction "1_1") (pintype "passive"))
      (node (ref "R18") (pin "1") (pinfunction "1_1") (pintype "passive"))
      (node (ref "R45") (pin "2") (pinfunction "2_2") (pintype "passive"))
      (node (ref "R53") (pin "1") (pinfunction "1_1") (pintype "passive"))
      (node (ref "U8") (pin "26") (pinfunction "VS_26") (pintype "bidirectional"))
      (node (ref "U8") (pin "27") (pinfunction "VS_27") (pintype "bidirectional"))
      (node (ref "U8") (pin "34") (pinfunction "VS_34") (pintype "bidirectional"))
      (node (ref "U8") (pin "35") (pinfunction "VS_35") (pintype "bidirectional"))
      (node (ref "U9") (pin "26") (pinfunction "VS_26") (pintype "bidirectional"))
      (node (ref "U9") (pin "27") (pinfunction "VS_27") (pintype "bidirectional"))
      (node (ref "U9") (pin "34") (pinfunction "VS_34") (pintype "bidirectional"))
      (node (ref "U9") (pin "35") (pinfunction "VS_35") (pintype "bidirectional"))
    )
    (net (code "92") (name "5V") (class "Default")
      (node (ref "C15") (pin "1") (pinfunction "1_1") (pintype "passive"))
      (node (ref "C28") (pin "1") (pinfunction "1_1") (pintype "passive"))
      (node (ref "C32") (pin "1") (pinfunction "1_1") (pintype "passive"))
      (node (ref "C52") (pin "+") (pinfunction "+_+") (pintype "passive"))
      (node (ref "J8") (pin "6") (pinfunction "6_6") (pintype "passive"))
      (node (ref "JP1") (pin "3") (pinfunction "3_3") (pintype "passive"))
      (node (ref "L1") (pin "P$2") (pinfunction "2_P$2") (pintype "passive"))
      (node (ref "LCD") (pin "VDD") (pinfunction "VDD_VDD") (pintype "bidirectional"))
      (node (ref "LS1") (pin "+") (pinfunction "1_+") (pintype "passive"))
      (node (ref "POT") (pin "1") (pinfunction "A_1") (pintype "passive"))
      (node (ref "Q5") (pin "4") (pinfunction "S_4") (pintype "bidirectional"))
      (node (ref "Q5") (pin "7") (pinfunction "S_7") (pintype "bidirectional"))
      (node (ref "Q6") (pin "4") (pinfunction "S_4") (pintype "bidirectional"))
      (node (ref "Q6") (pin "7") (pinfunction "S_7") (pintype "bidirectional"))
      (node (ref "Q7") (pin "5") (pinfunction "D_5") (pintype "bidirectional"))
      (node (ref "Q7") (pin "6") (pinfunction "D_6") (pintype "bidirectional"))
      (node (ref "Q7") (pin "7") (pinfunction "D_7") (pintype "bidirectional"))
      (node (ref "Q7") (pin "8") (pinfunction "D_8") (pintype "bidirectional"))
      (node (ref "Q7") (pin "PAD") (pinfunction "D_PAD") (pintype "bidirectional"))
      (node (ref "R1") (pin "2") (pinfunction "2_2") (pintype "passive"))
      (node (ref "R27") (pin "2") (pinfunction "2_2") (pintype "passive"))
      (node (ref "R33") (pin "1") (pinfunction "1_1") (pintype "passive"))
      (node (ref "R34") (pin "1") (pinfunction "1_1") (pintype "passive"))
      (node (ref "R44") (pin "2") (pinfunction "2_2") (pintype "passive"))
      (node (ref "R9") (pin "2") (pinfunction "2_2") (pintype "passive"))
      (node (ref "U1") (pin "29") (pinfunction "OUT5_29") (pintype "bidirectional"))
      (node (ref "U12") (pin "14") (pinfunction "VCC_14") (pintype "bidirectional"))
      (node (ref "U12") (pin "9") (pinfunction "/RST_9") (pintype "bidirectional"))
      (node (ref "U2") (pin "8") (pinfunction "V+_8") (pintype "power_in"))
      (node (ref "U5") (pin "2") (pinfunction "VIN_2") (pintype "bidirectional"))
      (node (ref "U5") (pin "3") (pinfunction "VIN_3") (pintype "bidirectional"))
      (node (ref "U7") (pin "5") (pinfunction "VCC_5") (pintype "bidirectional"))
    )
    (net (code "93") (name "GND") (class "Default")
      (node (ref "BTN0") (pin "3") (pinfunction "P_3") (pintype "passive"))
      (node (ref "BTN0") (pin "4") (pinfunction "P1_4") (pintype "passive"))
      (node (ref "BTN1") (pin "3") (pinfunction "P_3") (pintype "passive"))
      (node (ref "BTN1") (pin "4") (pinfunction "P1_4") (pintype "passive"))
      (node (ref "C1") (pin "2") (pinfunction "2_2") (pintype "passive"))
      (node (ref "C10") (pin "2") (pinfunction "2_2") (pintype "passive"))
      (node (ref "C11") (pin "2") (pinfunction "2_2") (pintype "passive"))
      (node (ref "C12") (pin "2") (pinfunction "2_2") (pintype "passive"))
      (node (ref "C13") (pin "2") (pinfunction "2_2") (pintype "passive"))
      (node (ref "C14") (pin "2") (pinfunction "2_2") (pintype "passive"))
      (node (ref "C15") (pin "2") (pinfunction "2_2") (pintype "passive"))
      (node (ref "C16") (pin "2") (pinfunction "2_2") (pintype "passive"))
      (node (ref "C17") (pin "2") (pinfunction "2_2") (pintype "passive"))
      (node (ref "C18") (pin "2") (pinfunction "2_2") (pintype "passive"))
      (node (ref "C19") (pin "2") (pinfunction "2_2") (pintype "passive"))
      (node (ref "C2") (pin "2") (pinfunction "2_2") (pintype "passive"))
      (node (ref "C21") (pin "2") (pinfunction "2_2") (pintype "passive"))
      (node (ref "C22") (pin "1") (pinfunction "1_1") (pintype "passive"))
      (node (ref "C23") (pin "2") (pinfunction "2_2") (pintype "passive"))
      (node (ref "C24") (pin "1") (pinfunction "1_1") (pintype "passive"))
      (node (ref "C25") (pin "2") (pinfunction "2_2") (pintype "passive"))
      (node (ref "C26") (pin "2") (pinfunction "2_2") (pintype "passive"))
      (node (ref "C27") (pin "2") (pinfunction "2_2") (pintype "passive"))
      (node (ref "C28") (pin "2") (pinfunction "2_2") (pintype "passive"))
      (node (ref "C3") (pin "2") (pinfunction "2_2") (pintype "passive"))
      (node (ref "C31") (pin "2") (pinfunction "2_2") (pintype "passive"))
      (node (ref "C32") (pin "2") (pinfunction "2_2") (pintype "passive"))
      (node (ref "C33") (pin "2") (pinfunction "2_2") (pintype "passive"))
      (node (ref "C34") (pin "2") (pinfunction "2_2") (pintype "passive"))
      (node (ref "C35") (pin "2") (pinfunction "2_2") (pintype "passive"))
      (node (ref "C37") (pin "2") (pinfunction "2_2") (pintype "passive"))
      (node (ref "C39") (pin "2") (pinfunction "2_2") (pintype "passive"))
      (node (ref "C4") (pin "2") (pinfunction "2_2") (pintype "passive"))
      (node (ref "C40") (pin "2") (pinfunction "2_2") (pintype "passive"))
      (node (ref "C41") (pin "2") (pinfunction "2_2") (pintype "passive"))
      (node (ref "C42") (pin "2") (pinfunction "2_2") (pintype "passive"))
      (node (ref "C43") (pin "2") (pinfunction "2_2") (pintype "passive"))
      (node (ref "C44") (pin "-") (pinfunction "-_-") (pintype "passive"))
      (node (ref "C46") (pin "2") (pinfunction "2_2") (pintype "passive"))
      (node (ref "C47") (pin "2") (pinfunction "2_2") (pintype "passive"))
      (node (ref "C5") (pin "2") (pinfunction "2_2") (pintype "passive"))
      (node (ref "C50") (pin "2") (pinfunction "2_2") (pintype "passive"))
      (node (ref "C52") (pin "-") (pinfunction "-_-") (pintype "passive"))
      (node (ref "C53") (pin "2") (pinfunction "2_2") (pintype "passive"))
      (node (ref "C57") (pin "2") (pinfunction "2_2") (pintype "passive"))
      (node (ref "C59") (pin "2") (pinfunction "2_2") (pintype "passive"))
      (node (ref "C6") (pin "2") (pinfunction "2_2") (pintype "passive"))
      (node (ref "C60") (pin "2") (pinfunction "2_2") (pintype "passive"))
      (node (ref "C61") (pin "2") (pinfunction "2_2") (pintype "passive"))
      (node (ref "C7") (pin "2") (pinfunction "2_2") (pintype "passive"))
      (node (ref "C9") (pin "2") (pinfunction "2_2") (pintype "passive"))
      (node (ref "D10") (pin "C") (pinfunction "C_C") (pintype "passive"))
      (node (ref "D2") (pin "P$1") (pinfunction "A_P$1") (pintype "passive"))
      (node (ref "D3") (pin "P$1") (pinfunction "A_P$1") (pintype "passive"))
      (node (ref "D8") (pin "C") (pinfunction "C_C") (pintype "passive"))
      (node (ref "D9") (pin "C") (pinfunction "C_C") (pintype "passive"))
      (node (ref "J1") (pin "4") (pinfunction "4_4") (pintype "passive"))
      (node (ref "J12") (pin "1") (pinfunction "1_1") (pintype "passive"))
      (node (ref "J12") (pin "10") (pinfunction "10_10") (pintype "passive"))
      (node (ref "J12") (pin "11") (pinfunction "11_11") (pintype "passive"))
      (node (ref "J12") (pin "12") (pinfunction "12_12") (pintype "passive"))
      (node (ref "J12") (pin "13") (pinfunction "13_13") (pintype "passive"))
      (node (ref "J12") (pin "14") (pinfunction "14_14") (pintype "passive"))
      (node (ref "J12") (pin "15") (pinfunction "15_15") (pintype "passive"))
      (node (ref "J12") (pin "2") (pinfunction "2_2") (pintype "passive"))
      (node (ref "J12") (pin "3") (pinfunction "3_3") (pintype "passive"))
      (node (ref "J12") (pin "4") (pinfunction "4_4") (pintype "passive"))
      (node (ref "J12") (pin "5") (pinfunction "5_5") (pintype "passive"))
      (node (ref "J12") (pin "6") (pinfunction "6_6") (pintype "passive"))
      (node (ref "J12") (pin "7") (pinfunction "7_7") (pintype "passive"))
      (node (ref "J12") (pin "8") (pinfunction "8_8") (pintype "passive"))
      (node (ref "J12") (pin "9") (pinfunction "9_9") (pintype "passive"))
      (node (ref "J15") (pin "1") (pinfunction "1_1") (pintype "passive"))
      (node (ref "J15") (pin "2") (pinfunction "2_2") (pintype "passive"))
      (node (ref "J15") (pin "3") (pinfunction "3_3") (pintype "passive"))
      (node (ref "J15") (pin "4") (pinfunction "4_4") (pintype "passive"))
      (node (ref "J15") (pin "5") (pinfunction "5_5") (pintype "passive"))
      (node (ref "J15") (pin "6") (pinfunction "6_6") (pintype "passive"))
      (node (ref "J15") (pin "7") (pinfunction "7_7") (pintype "passive"))
      (node (ref "J15") (pin "8") (pinfunction "8_8") (pintype "passive"))
      (node (ref "J2") (pin "3") (pinfunction "3_3") (pintype "passive"))
      (node (ref "J3") (pin "3") (pinfunction "3_3") (pintype "passive"))
      (node (ref "J4") (pin "3") (pinfunction "3_3") (pintype "passive"))
      (node (ref "J5") (pin "2") (pinfunction "2_2") (pintype "passive"))
      (node (ref "J6") (pin "3") (pinfunction "3_3") (pintype "passive"))
      (node (ref "J7") (pin "3") (pinfunction "3_3") (pintype "passive"))
      (node (ref "J8") (pin "7") (pinfunction "7_7") (pintype "passive"))
      (node (ref "J9") (pin "1") (pinfunction "1_1") (pintype "passive"))
      (node (ref "J9") (pin "2") (pinfunction "2_2") (pintype "passive"))
      (node (ref "J9") (pin "3") (pinfunction "3_3") (pintype "passive"))
      (node (ref "J9") (pin "4") (pinfunction "4_4") (pintype "passive"))
      (node (ref "J9") (pin "5") (pinfunction "5_5") (pintype "passive"))
      (node (ref "J9") (pin "6") (pinfunction "6_6") (pintype "passive"))
      (node (ref "J9") (pin "7") (pinfunction "7_7") (pintype "passive"))
      (node (ref "J9") (pin "8") (pinfunction "8_8") (pintype "passive"))
      (node (ref "LCD") (pin "K") (pinfunction "K_K") (pintype "bidirectional"))
      (node (ref "LCD") (pin "R/W") (pinfunction "R/W_R/W") (pintype "bidirectional"))
      (node (ref "LCD") (pin "VSS") (pinfunction "VSS_VSS") (pintype "bidirectional"))
      (node (ref "POT") (pin "3") (pinfunction "E_3") (pintype "passive"))
      (node (ref "POWER") (pin "R") (pinfunction "R_R") (pintype "bidirectional"))
      (node (ref "Q3") (pin "5/6/7") (pinfunction "S2_5/6/7") (pintype "bidirectional"))
      (node (ref "Q4") (pin "5/6/7") (pinfunction "S2_5/6/7") (pintype "bidirectional"))
      (node (ref "Q9") (pin "2") (pinfunction "E_2") (pintype "passive"))
      (node (ref "R10") (pin "1") (pinfunction "1_1") (pintype "passive"))
      (node (ref "R11") (pin "1") (pinfunction "1_1") (pintype "passive"))
      (node (ref "R19") (pin "2") (pinfunction "2_2") (pintype "passive"))
      (node (ref "R2") (pin "2") (pinfunction "2_2") (pintype "passive"))
      (node (ref "R26") (pin "1") (pinfunction "1_1") (pintype "passive"))
      (node (ref "R28") (pin "2") (pinfunction "2_2") (pintype "passive"))
      (node (ref "R30") (pin "2") (pinfunction "2_2") (pintype "passive"))
      (node (ref "R35") (pin "1") (pinfunction "1_1") (pintype "passive"))
      (node (ref "R41") (pin "2") (pinfunction "2_2") (pintype "passive"))
      (node (ref "R42") (pin "1") (pinfunction "1_1") (pintype "passive"))
      (node (ref "R43") (pin "1") (pinfunction "1_1") (pintype "passive"))
      (node (ref "RESET") (pin "3") (pinfunction "P_3") (pintype "passive"))
      (node (ref "RESET") (pin "4") (pinfunction "P1_4") (pintype "passive"))
      (node (ref "SERVO_PWR") (pin "R") (pinfunction "R_R") (pintype "bidirectional"))
      (node (ref "SW1") (pin "P$1") (pinfunction "P$1_P$1") (pintype "bidirectional"))
      (node (ref "SW1") (pin "P$3") (pinfunction "P$1_P$3") (pintype "bidirectional"))
      (node (ref "U1") (pin "1") (pinfunction "SGND_1") (pintype "bidirectional"))
      (node (ref "U1") (pin "14") (pinfunction "PGND_14") (pintype "bidirectional"))
      (node (ref "U1") (pin "16") (pinfunction "SGND2_16") (pintype "bidirectional"))
      (node (ref "U1") (pin "17") (pinfunction "V5SW_17") (pintype "bidirectional"))
      (node (ref "U1") (pin "24") (pinfunction "SKIP_24") (pintype "bidirectional"))
      (node (ref "U1") (pin "28") (pinfunction "LDO3SEL_28") (pintype "bidirectional"))
      (node (ref "U1") (pin "PAD") (pinfunction "PGND_PAD") (pintype "bidirectional"))
      (node (ref "U10") (pin "10") (pinfunction "VSS_5_10") (pintype "power_in"))
      (node (ref "U10") (pin "20") (pinfunction "VSSA_20") (pintype "power_in"))
      (node (ref "U10") (pin "27") (pinfunction "VSS_4_27") (pintype "power_in"))
      (node (ref "U10") (pin "74") (pinfunction "VSS_2_74") (pintype "power_in"))
      (node (ref "U10") (pin "99") (pinfunction "VSS_6_99") (pintype "power_in"))
      (node (ref "U11") (pin "14") (pinfunction "GND_14") (pintype "bidirectional"))
      (node (ref "U11") (pin "15") (pinfunction "GND_15") (pintype "bidirectional"))
      (node (ref "U11") (pin "16") (pinfunction "GND_16") (pintype "bidirectional"))
      (node (ref "U11") (pin "17") (pinfunction "GND_17") (pintype "bidirectional"))
      (node (ref "U11") (pin "18") (pinfunction "GND_18") (pintype "bidirectional"))
      (node (ref "U11") (pin "19") (pinfunction "GND_19") (pintype "bidirectional"))
      (node (ref "U11") (pin "20") (pinfunction "GND_20") (pintype "bidirectional"))
      (node (ref "U11") (pin "5") (pinfunction "SA0_5") (pintype "bidirectional"))
      (node (ref "U11") (pin "6") (pinfunction "SA0_6") (pintype "bidirectional"))
      (node (ref "U12") (pin "7") (pinfunction "GND_7") (pintype "bidirectional"))
      (node (ref "U2") (pin "4") (pinfunction "V-_4") (pintype "power_in"))
      (node (ref "U3") (pin "1") (pinfunction "GND_1") (pintype "bidirectional"))
      (node (ref "U4") (pin "P$2") (pinfunction "GND_P$2") (pintype "bidirectional"))
      (node (ref "U5") (pin "1") (pinfunction "GND_1") (pintype "bidirectional"))
      (node (ref "U6") (pin "P$2") (pinfunction "GND_P$2") (pintype "bidirectional"))
      (node (ref "U7") (pin "3") (pinfunction "GND_3") (pintype "bidirectional"))
      (node (ref "U8") (pin "1") (pinfunction "GND_1") (pintype "bidirectional"))
      (node (ref "U8") (pin "12") (pinfunction "GND_12") (pintype "bidirectional"))
      (node (ref "U8") (pin "14") (pinfunction "GND_14") (pintype "bidirectional"))
      (node (ref "U8") (pin "15") (pinfunction "SENSE_B_15") (pintype "bidirectional"))
      (node (ref "U8") (pin "16") (pinfunction "SENSE_B_16") (pintype "bidirectional"))
      (node (ref "U8") (pin "19") (pinfunction "PROGCLB_19") (pintype "bidirectional"))
      (node (ref "U8") (pin "24") (pinfunction "GND_24") (pintype "bidirectional"))
      (node (ref "U8") (pin "25") (pinfunction "GND_25") (pintype "bidirectional"))
      (node (ref "U8") (pin "28") (pinfunction "GND_28") (pintype "bidirectional"))
      (node (ref "U8") (pin "29") (pinfunction "GND_29") (pintype "bidirectional"))
      (node (ref "U8") (pin "30") (pinfunction "GND_30") (pintype "bidirectional"))
      (node (ref "U8") (pin "31") (pinfunction "GND_31") (pintype "bidirectional"))
      (node (ref "U8") (pin "32") (pinfunction "GND_32") (pintype "bidirectional"))
      (node (ref "U8") (pin "33") (pinfunction "GND_33") (pintype "bidirectional"))
      (node (ref "U8") (pin "36") (pinfunction "GND_36") (pintype "bidirectional"))
      (node (ref "U8") (pin "37") (pinfunction "GND_37") (pintype "bidirectional"))
      (node (ref "U8") (pin "4") (pinfunction "GND_4") (pintype "bidirectional"))
      (node (ref "U8") (pin "42") (pinfunction "PROGCLA_42") (pintype "bidirectional"))
      (node (ref "U8") (pin "45") (pinfunction "SENSE_A_45") (pintype "bidirectional"))
      (node (ref "U8") (pin "46") (pinfunction "SENSE_A_46") (pintype "bidirectional"))
      (node (ref "U8") (pin "47") (pinfunction "GND_47") (pintype "bidirectional"))
      (node (ref "U8") (pin "5") (pinfunction "GND_5") (pintype "bidirectional"))
      (node (ref "U8") (pin "6") (pinfunction "GND_6") (pintype "bidirectional"))
      (node (ref "U8") (pin "7") (pinfunction "GND_7") (pintype "bidirectional"))
      (node (ref "U8") (pin "8") (pinfunction "GND_8") (pintype "bidirectional"))
      (node (ref "U8") (pin "9") (pinfunction "GND_9") (pintype "bidirectional"))
      (node (ref "U8") (pin "PAD") (pinfunction "GND_PAD") (pintype "bidirectional"))
      (node (ref "U9") (pin "1") (pinfunction "GND_1") (pintype "bidirectional"))
      (node (ref "U9") (pin "12") (pinfunction "GND_12") (pintype "bidirectional"))
      (node (ref "U9") (pin "14") (pinfunction "GND_14") (pintype "bidirectional"))
      (node (ref "U9") (pin "15") (pinfunction "SENSE_B_15") (pintype "bidirectional"))
      (node (ref "U9") (pin "16") (pinfunction "SENSE_B_16") (pintype "bidirectional"))
      (node (ref "U9") (pin "19") (pinfunction "PROGCLB_19") (pintype "bidirectional"))
      (node (ref "U9") (pin "24") (pinfunction "GND_24") (pintype "bidirectional"))
      (node (ref "U9") (pin "25") (pinfunction "GND_25") (pintype "bidirectional"))
      (node (ref "U9") (pin "28") (pinfunction "GND_28") (pintype "bidirectional"))
      (node (ref "U9") (pin "29") (pinfunction "GND_29") (pintype "bidirectional"))
      (node (ref "U9") (pin "30") (pinfunction "GND_30") (pintype "bidirectional"))
      (node (ref "U9") (pin "31") (pinfunction "GND_31") (pintype "bidirectional"))
      (node (ref "U9") (pin "32") (pinfunction "GND_32") (pintype "bidirectional"))
      (node (ref "U9") (pin "33") (pinfunction "GND_33") (pintype "bidirectional"))
      (node (ref "U9") (pin "36") (pinfunction "GND_36") (pintype "bidirectional"))
      (node (ref "U9") (pin "37") (pinfunction "GND_37") (pintype "bidirectional"))
      (node (ref "U9") (pin "4") (pinfunction "GND_4") (pintype "bidirectional"))
      (node (ref "U9") (pin "42") (pinfunction "PROGCLA_42") (pintype "bidirectional"))
      (node (ref "U9") (pin "45") (pinfunction "SENSE_A_45") (pintype "bidirectional"))
      (node (ref "U9") (pin "46") (pinfunction "SENSE_A_46") (pintype "bidirectional"))
      (node (ref "U9") (pin "47") (pinfunction "GND_47") (pintype "bidirectional"))
      (node (ref "U9") (pin "5") (pinfunction "GND_5") (pintype "bidirectional"))
      (node (ref "U9") (pin "6") (pinfunction "GND_6") (pintype "bidirectional"))
      (node (ref "U9") (pin "7") (pinfunction "GND_7") (pintype "bidirectional"))
      (node (ref "U9") (pin "8") (pinfunction "GND_8") (pintype "bidirectional"))
      (node (ref "U9") (pin "9") (pinfunction "GND_9") (pintype "bidirectional"))
      (node (ref "U9") (pin "PAD") (pinfunction "GND_PAD") (pintype "bidirectional"))
      (node (ref "USB1") (pin "GND") (pinfunction "GND_GND") (pintype "bidirectional"))
      (node (ref "USB1") (pin "GND@1") (pinfunction "GND_GND@1") (pintype "bidirectional"))
      (node (ref "USB1") (pin "GND@2") (pinfunction "GND_GND@2") (pintype "bidirectional"))
      (node (ref "USB2") (pin "GND") (pinfunction "GND_GND") (pintype "bidirectional"))
      (node (ref "USB2") (pin "MTN1") (pinfunction "MTN2_MTN1") (pintype "bidirectional"))
      (node (ref "USB2") (pin "MTN2") (pinfunction "MTN3_MTN2") (pintype "bidirectional"))
      (node (ref "USB2") (pin "MTN3") (pinfunction "MTN1_MTN3") (pintype "bidirectional"))
      (node (ref "USB2") (pin "MTN4") (pinfunction "MTN4_MTN4") (pintype "bidirectional"))
      (node (ref "USD") (pin "6") (pinfunction "GND_6") (pintype "bidirectional"))
      (node (ref "USD") (pin "GND3") (pinfunction "SHIELD_GND3") (pintype "bidirectional"))
      (node (ref "XB1") (pin "10") (pinfunction "GND_10") (pintype "power_in"))
    )
    (net (code "94") (name "Net-(C8-Pad1)") (class "Default")
      (node (ref "C8") (pin "1") (pinfunction "1_1") (pintype "passive"))
      (node (ref "D1") (pin "P$1") (pinfunction "P$1_P$1") (pintype "output"))
      (node (ref "R51") (pin "2") (pinfunction "2_2") (pintype "passive"))
    )
    (net (code "95") (name "Net-(C21-Pad1)") (class "Default")
      (node (ref "C21") (pin "1") (pinfunction "1_1") (pintype "passive"))
      (node (ref "C23") (pin "1") (pinfunction "1_1") (pintype "passive"))
      (node (ref "U5") (pin "6") (pinfunction "VOUT_6") (pintype "bidirectional"))
      (node (ref "U5") (pin "7") (pinfunction "VOUT_7") (pintype "bidirectional"))
      (node (ref "U5") (pin "8") (pinfunction "VOUT_8") (pintype "bidirectional"))
      (node (ref "USB1") (pin "VBUS") (pinfunction "VBUS_VBUS") (pintype "bidirectional"))
    )
    (net (code "96") (name "Net-(C29-Pad1)") (class "Default")
      (node (ref "C29") (pin "1") (pinfunction "1_1") (pintype "passive"))
      (node (ref "Q1") (pin "1") (pinfunction "S_1") (pintype "bidirectional"))
      (node (ref "Q1") (pin "2") (pinfunction "S_2") (pintype "bidirectional"))
      (node (ref "Q1") (pin "3") (pinfunction "S_3") (pintype "bidirectional"))
      (node (ref "Q2") (pin "1") (pinfunction "S_1") (pintype "bidirectional"))
      (node (ref "Q2") (pin "2") (pinfunction "S_2") (pintype "bidirectional"))
      (node (ref "Q2") (pin "3") (pinfunction "S_3") (pintype "bidirectional"))
      (node (ref "R3") (pin "2") (pinfunction "2_2") (pintype "passive"))
    )
    (net (code "97") (name "Net-(C45-Pad1)") (class "Default")
      (node (ref "C45") (pin "1") (pinfunction "1_1") (pintype "passive"))
      (node (ref "R12") (pin "1") (pinfunction "1_1") (pintype "passive"))
    )
    (net (code "98") (name "Net-(C49-Pad1)") (class "Default")
      (node (ref "C49") (pin "1") (pinfunction "1_1") (pintype "passive"))
      (node (ref "R13") (pin "1") (pinfunction "1_1") (pintype "passive"))
    )
    (net (code "99") (name "Net-(C54-Pad2)") (class "Default")
      (node (ref "C54") (pin "2") (pinfunction "2_2") (pintype "passive"))
      (node (ref "R9") (pin "1") (pinfunction "1_1") (pintype "passive"))
    )
    (net (code "100") (name "Net-(C58-Pad2)") (class "Default")
      (node (ref "C58") (pin "2") (pinfunction "2_2") (pintype "passive"))
      (node (ref "R15") (pin "1") (pinfunction "1_1") (pintype "passive"))
    )
    (net (code "101") (name "Net-(D4-Pad2)") (class "Default")
      (node (ref "D4") (pin "2") (pinfunction "2_2") (pintype "bidirectional"))
      (node (ref "R13") (pin "2") (pinfunction "2_2") (pintype "passive"))
    )
    (net (code "102") (name "Net-(D5-Pad2)") (class "Default")
      (node (ref "D5") (pin "2") (pinfunction "2_2") (pintype "bidirectional"))
      (node (ref "R12") (pin "2") (pinfunction "2_2") (pintype "passive"))
    )
    (net (code "103") (name "Net-(D6-Pad1)") (class "Default")
      (node (ref "D6") (pin "1") (pinfunction "1_1") (pintype "passive"))
      (node (ref "D6") (pin "4") (pinfunction "4_4") (pintype "passive"))
      (node (ref "R38") (pin "2") (pinfunction "2_2") (pintype "passive"))
    )
    (net (code "104") (name "Net-(D7-Pad1)") (class "Default")
      (node (ref "D7") (pin "1") (pinfunction "1_1") (pintype "passive"))
      (node (ref "D7") (pin "4") (pinfunction "4_4") (pintype "passive"))
      (node (ref "R37") (pin "2") (pinfunction "2_2") (pintype "passive"))
    )
    (net (code "105") (name "Net-(D8-PadA)") (class "Default")
      (node (ref "D8") (pin "A") (pinfunction "A_A") (pintype "passive"))
      (node (ref "R4") (pin "1") (pinfunction "1_1") (pintype "passive"))
    )
    (net (code "106") (name "Net-(D9-PadA)") (class "Default")
      (node (ref "D9") (pin "A") (pinfunction "A_A") (pintype "passive"))
      (node (ref "R20") (pin "1") (pinfunction "1_1") (pintype "passive"))
    )
    (net (code "107") (name "Net-(D10-PadA)") (class "Default")
      (node (ref "D10") (pin "A") (pinfunction "A_A") (pintype "passive"))
      (node (ref "R21") (pin "1") (pinfunction "1_1") (pintype "passive"))
    )
    (net (code "108") (name "Net-(D11-PadC)") (class "Default")
      (node (ref "D11") (pin "C") (pinfunction "C_C") (pintype "passive"))
      (node (ref "R35") (pin "2") (pinfunction "2_2") (pintype "passive"))
    )
    (net (code "109") (name "Net-(F1-Pad1)") (class "Default")
      (node (ref "F1") (pin "1") (pinfunction "1_1") (pintype "bidirectional"))
      (node (ref "Q5") (pin "1") (pinfunction "D_1") (pintype "bidirectional"))
      (node (ref "Q5") (pin "2") (pinfunction "D_2") (pintype "bidirectional"))
      (node (ref "Q5") (pin "5") (pinfunction "D_5") (pintype "bidirectional"))
      (node (ref "Q5") (pin "6") (pinfunction "D_6") (pintype "bidirectional"))
      (node (ref "Q5") (pin "8") (pinfunction "D_8") (pintype "bidirectional"))
    )
    (net (code "110") (name "Net-(J13-Pad1)") (class "Default")
      (node (ref "J13") (pin "1") (pinfunction "1_1") (pintype "passive"))
      (node (ref "J13") (pin "10") (pinfunction "10_10") (pintype "passive"))
      (node (ref "J13") (pin "11") (pinfunction "11_11") (pintype "passive"))
      (node (ref "J13") (pin "12") (pinfunction "12_12") (pintype "passive"))
      (node (ref "J13") (pin "13") (pinfunction "13_13") (pintype "passive"))
      (node (ref "J13") (pin "14") (pinfunction "14_14") (pintype "passive"))
      (node (ref "J13") (pin "15") (pinfunction "15_15") (pintype "passive"))
      (node (ref "J13") (pin "2") (pinfunction "2_2") (pintype "passive"))
      (node (ref "J13") (pin "3") (pinfunction "3_3") (pintype "passive"))
      (node (ref "J13") (pin "4") (pinfunction "4_4") (pintype "passive"))
      (node (ref "J13") (pin "5") (pinfunction "5_5") (pintype "passive"))
      (node (ref "J13") (pin "6") (pinfunction "6_6") (pintype "passive"))
      (node (ref "J13") (pin "7") (pinfunction "7_7") (pintype "passive"))
      (node (ref "J13") (pin "8") (pinfunction "8_8") (pintype "passive"))
      (node (ref "J13") (pin "9") (pinfunction "9_9") (pintype "passive"))
      (node (ref "JP1") (pin "2") (pinfunction "2_2") (pintype "passive"))
    )
    (net (code "111") (name "Net-(L1-1)") (class "Default")
      (node (ref "C8") (pin "2") (pinfunction "2_2") (pintype "passive"))
      (node (ref "D2") (pin "C2") (pinfunction "C_C2") (pintype "passive"))
      (node (ref "D2") (pin "P$2") (pinfunction "C_P$2") (pintype "passive"))
      (node (ref "L1") (pin "P$1") (pinfunction "1_P$1") (pintype "passive"))
      (node (ref "Q3") (pin "S1D2") (pinfunction "S1_S1D2") (pintype "bidirectional"))
      (node (ref "R8") (pin "1") (pinfunction "1_1") (pintype "passive"))
      (node (ref "U1") (pin "21") (pinfunction "PHASE5_21") (pintype "bidirectional"))
    )
    (net (code "112") (name "Net-(L2-1)") (class "Default")
      (node (ref "C55") (pin "2") (pinfunction "2_2") (pintype "passive"))
      (node (ref "D3") (pin "C2") (pinfunction "C_C2") (pintype "passive"))
      (node (ref "D3") (pin "P$2") (pinfunction "C_P$2") (pintype "passive"))
      (node (ref "L2") (pin "P$1") (pinfunction "1_P$1") (pintype "passive"))
      (node (ref "Q4") (pin "S1D2") (pinfunction "S1_S1D2") (pintype "bidirectional"))
      (node (ref "R14") (pin "1") (pinfunction "1_1") (pintype "passive"))
      (node (ref "U1") (pin "11") (pinfunction "PHASE3_11") (pintype "bidirectional"))
    )
    (net (code "113") (name "Net-(LCD-PadA)") (class "Default")
      (node (ref "LCD") (pin "A") (pinfunction "A_A") (pintype "bidirectional"))
      (node (ref "R1") (pin "1") (pinfunction "1_1") (pintype "passive"))
    )
    (net (code "114") (name "Net-(LS1-2)") (class "Default")
      (node (ref "LS1") (pin "-") (pinfunction "2_-") (pintype "passive"))
      (node (ref "Q9") (pin "3") (pinfunction "C_3") (pintype "passive"))
    )
    (net (code "115") (name "Net-(POT-S)") (class "Default")
      (node (ref "LCD") (pin "VO") (pinfunction "VO_VO") (pintype "bidirectional"))
      (node (ref "POT") (pin "2") (pinfunction "S_2") (pintype "passive"))
    )
    (net (code "116") (name "Net-(POWER-PadL)") (class "Default")
      (node (ref "POWER") (pin "L") (pinfunction "L_L") (pintype "bidirectional"))
      (node (ref "Q1") (pin "5") (pinfunction "D_5") (pintype "bidirectional"))
      (node (ref "Q1") (pin "6") (pinfunction "D_6") (pintype "bidirectional"))
      (node (ref "Q1") (pin "7") (pinfunction "D_7") (pintype "bidirectional"))
      (node (ref "Q1") (pin "8") (pinfunction "D_8") (pintype "bidirectional"))
      (node (ref "Q1") (pin "PAD") (pinfunction "D_PAD") (pintype "bidirectional"))
    )
    (net (code "117") (name "Net-(Q1-G)") (class "Default")
      (node (ref "C29") (pin "2") (pinfunction "2_2") (pintype "passive"))
      (node (ref "Q1") (pin "4") (pinfunction "G_4") (pintype "bidirectional"))
      (node (ref "R2") (pin "1") (pinfunction "1_1") (pintype "passive"))
    )
    (net (code "118") (name "Net-(Q2-G)") (class "Default")
      (node (ref "Q2") (pin "4") (pinfunction "G_4") (pintype "bidirectional"))
      (node (ref "R3") (pin "1") (pinfunction "1_1") (pintype "passive"))
      (node (ref "R31") (pin "1") (pinfunction "1_1") (pintype "passive"))
    )
    (net (code "119") (name "Net-(Q3-G1)") (class "Default")
      (node (ref "Q3") (pin "1") (pinfunction "G1_1") (pintype "bidirectional"))
      (node (ref "U1") (pin "22") (pinfunction "HGATE5_22") (pintype "bidirectional"))
    )
    (net (code "120") (name "Net-(Q3-G2)") (class "Default")
      (node (ref "Q3") (pin "8") (pinfunction "G2_8") (pintype "bidirectional"))
      (node (ref "U1") (pin "15") (pinfunction "LGATE5_15") (pintype "bidirectional"))
    )
    (net (code "121") (name "Net-(Q4-G1)") (class "Default")
      (node (ref "Q4") (pin "1") (pinfunction "G1_1") (pintype "bidirectional"))
      (node (ref "U1") (pin "10") (pinfunction "HGATE3_10") (pintype "bidirectional"))
    )
    (net (code "122") (name "Net-(Q4-G2)") (class "Default")
      (node (ref "Q4") (pin "8") (pinfunction "G2_8") (pintype "bidirectional"))
      (node (ref "U1") (pin "13") (pinfunction "LGATE3_13") (pintype "bidirectional"))
    )
    (net (code "123") (name "Net-(Q5-G)") (class "Default")
      (node (ref "Q5") (pin "3") (pinfunction "G_3") (pintype "bidirectional"))
      (node (ref "Q6") (pin "3") (pinfunction "G_3") (pintype "bidirectional"))
      (node (ref "U2") (pin "1") (pinfunction "OUT_1") (pintype "output"))
    )
    (net (code "124") (name "Net-(Q7-G)") (class "Default")
      (node (ref "Q7") (pin "4") (pinfunction "G_4") (pintype "bidirectional"))
      (node (ref "R5") (pin "2") (pinfunction "2_2") (pintype "passive"))
    )
    (net (code "125") (name "Net-(Q8-G)") (class "Default")
      (node (ref "Q8") (pin "4") (pinfunction "G_4") (pintype "bidirectional"))
      (node (ref "R6") (pin "1") (pinfunction "1_1") (pintype "passive"))
    )
    (net (code "126") (name "Net-(Q9-B)") (class "Default")
      (node (ref "Q9") (pin "1") (pinfunction "B_1") (pintype "passive"))
      (node (ref "R39") (pin "2") (pinfunction "2_2") (pintype "passive"))
    )
    (net (code "127") (name "Net-(R31-Pad2)") (class "Default")
      (node (ref "R31") (pin "2") (pinfunction "2_2") (pintype "passive"))
      (node (ref "SW1") (pin "P$2") (pinfunction "P$2_P$2") (pintype "bidirectional"))
    )
    (net (code "128") (name "Net-(U1-BOOT3)") (class "Default")
      (node (ref "C55") (pin "1") (pinfunction "1_1") (pintype "passive"))
      (node (ref "R52") (pin "1") (pinfunction "1_1") (pintype "passive"))
      (node (ref "U1") (pin "9") (pinfunction "BOOT3_9") (pintype "bidirectional"))
    )
    (net (code "129") (name "Net-(U1-BOOT5)") (class "Default")
      (node (ref "R51") (pin "1") (pinfunction "1_1") (pintype "passive"))
      (node (ref "U1") (pin "23") (pinfunction "BOOT5_23") (pintype "bidirectional"))
    )
    (net (code "130") (name "Net-(U1-COMP3)") (class "Default")
      (node (ref "C57") (pin "1") (pinfunction "1_1") (pintype "passive"))
      (node (ref "C58") (pin "1") (pinfunction "1_1") (pintype "passive"))
      (node (ref "U1") (pin "2") (pinfunction "COMP3_2") (pintype "bidirectional"))
    )
    (net (code "131") (name "Net-(U1-COMP5)") (class "Default")
      (node (ref "C53") (pin "1") (pinfunction "1_1") (pintype "passive"))
      (node (ref "C54") (pin "1") (pinfunction "1_1") (pintype "passive"))
      (node (ref "U1") (pin "30") (pinfunction "COMP5_30") (pintype "bidirectional"))
    )
    (net (code "132") (name "Net-(U1-CSENSE3)") (class "Default")
      (node (ref "R14") (pin "2") (pinfunction "2_2") (pintype "passive"))
      (node (ref "U1") (pin "12") (pinfunction "CSENSE3_12") (pintype "bidirectional"))
    )
    (net (code "133") (name "Net-(U1-CSENSE5)") (class "Default")
      (node (ref "R8") (pin "2") (pinfunction "2_2") (pintype "passive"))
      (node (ref "U1") (pin "20") (pinfunction "CSENSE5_20") (pintype "bidirectional"))
    )
    (net (code "134") (name "Net-(U1-EN3)") (class "Default")
      (node (ref "R17") (pin "2") (pinfunction "2_2") (pintype "passive"))
      (node (ref "U1") (pin "4") (pinfunction "EN3_4") (pintype "bidirectional"))
    )
    (net (code "135") (name "Net-(U1-EN5)") (class "Default")
      (node (ref "R50") (pin "2") (pinfunction "2_2") (pintype "passive"))
      (node (ref "U1") (pin "25") (pinfunction "EN5_25") (pintype "bidirectional"))
    )
    (net (code "136") (name "Net-(U1-SHUDN)") (class "Default")
      (node (ref "R30") (pin "1") (pinfunction "1_1") (pintype "passive"))
      (node (ref "R53") (pin "2") (pinfunction "2_2") (pintype "passive"))
      (node (ref "U1") (pin "5") (pinfunction "SHUDN_5") (pintype "bidirectional"))
    )
    (net (code "137") (name "Net-(U1-VCC)") (class "Default")
      (node (ref "C5") (pin "1") (pinfunction "1_1") (pintype "passive"))
      (node (ref "R17") (pin "1") (pinfunction "1_1") (pintype "passive"))
      (node (ref "R32") (pin "1") (pinfunction "1_1") (pintype "passive"))
      (node (ref "R50") (pin "1") (pinfunction "1_1") (pintype "passive"))
      (node (ref "U1") (pin "31") (pinfunction "VCC_31") (pintype "bidirectional"))
    )
    (net (code "138") (name "Net-(U1-VIN)") (class "Default")
      (node (ref "C1") (pin "1") (pinfunction "1_1") (pintype "passive"))
      (node (ref "C59") (pin "1") (pinfunction "1_1") (pintype "passive"))
      (node (ref "R16") (pin "2") (pinfunction "2_2") (pintype "passive"))
      (node (ref "U1") (pin "19") (pinfunction "VIN_19") (pintype "bidirectional"))
    )
    (net (code "139") (name "Net-(U1-VREF)") (class "Default")
      (node (ref "C60") (pin "1") (pinfunction "1_1") (pintype "passive"))
      (node (ref "U1") (pin "32") (pinfunction "VREF_32") (pintype "bidirectional"))
    )
    (net (code "140") (name "Net-(U2A-+IN)") (class "Default")
      (node (ref "R11") (pin "2") (pinfunction "2_2") (pintype "passive"))
      (node (ref "R45") (pin "1") (pinfunction "1_1") (pintype "passive"))
      (node (ref "U2") (pin "3") (pinfunction "+IN_3") (pintype "input"))
    )
    (net (code "141") (name "Net-(U2A--IN)") (class "Default")
      (node (ref "R10") (pin "2") (pinfunction "2_2") (pintype "passive"))
      (node (ref "R44") (pin "1") (pinfunction "1_1") (pintype "passive"))
      (node (ref "U2") (pin "2") (pinfunction "-IN_2") (pintype "input"))
    )
    (net (code "142") (name "Net-(U2B-+IN)") (class "Default")
      (node (ref "R28") (pin "1") (pinfunction "1_1") (pintype "passive"))
      (node (ref "R29") (pin "2") (pinfunction "2_2") (pintype "passive"))
      (node (ref "U2") (pin "5") (pinfunction "+IN_5") (pintype "input"))
    )
    (net (code "143") (name "Net-(U2B--IN)") (class "Default")
      (node (ref "R26") (pin "2") (pinfunction "2_2") (pintype "passive"))
      (node (ref "R27") (pin "1") (pinfunction "1_1") (pintype "passive"))
      (node (ref "U2") (pin "6") (pinfunction "-IN_6") (pintype "input"))
    )
    (net (code "144") (name "Net-(U2B-OUT)") (class "Default")
      (node (ref "R36") (pin "1") (pinfunction "1_1") (pintype "passive"))
      (node (ref "U2") (pin "7") (pinfunction "OUT_7") (pintype "output"))
      (node (ref "U7") (pin "2") (pinfunction "A_2") (pintype "bidirectional"))
    )
    (net (code "145") (name "Net-(U3-VIN)") (class "Default")
      (node (ref "Q6") (pin "1") (pinfunction "D_1") (pintype "bidirectional"))
      (node (ref "Q6") (pin "2") (pinfunction "D_2") (pintype "bidirectional"))
      (node (ref "Q6") (pin "5") (pinfunction "D_5") (pintype "bidirectional"))
      (node (ref "Q6") (pin "6") (pinfunction "D_6") (pintype "bidirectional"))
      (node (ref "Q6") (pin "8") (pinfunction "D_8") (pintype "bidirectional"))
      (node (ref "U3") (pin "4") (pinfunction "VIN_4") (pintype "bidirectional"))
    )
    (net (code "146") (name "Net-(U4-IO1_1)") (class "Default")
      (node (ref "U4") (pin "P$1") (pinfunction "IO1_1_P$1") (pintype "bidirectional"))
      (node (ref "USB1") (pin "D-") (pinfunction "D-_D-") (pintype "bidirectional"))
    )
    (net (code "147") (name "Net-(U4-IO1_2)") (class "Default")
      (node (ref "R49") (pin "1") (pinfunction "1_1") (pintype "passive"))
      (node (ref "U4") (pin "P$6") (pinfunction "IO1_2_P$6") (pintype "bidirectional"))
    )
    (net (code "148") (name "Net-(U4-IO2_1)") (class "Default")
      (node (ref "U4") (pin "P$3") (pinfunction "IO2_1_P$3") (pintype "bidirectional"))
      (node (ref "USB1") (pin "D+") (pinfunction "D+_D+") (pintype "bidirectional"))
    )
    (net (code "149") (name "Net-(U4-IO2_2)") (class "Default")
      (node (ref "R48") (pin "1") (pinfunction "1_1") (pintype "passive"))
      (node (ref "U4") (pin "P$4") (pinfunction "IO2_2_P$4") (pintype "bidirectional"))
    )
    (net (code "150") (name "Net-(U6-IO1_1)") (class "Default")
      (node (ref "U6") (pin "P$1") (pinfunction "IO1_1_P$1") (pintype "bidirectional"))
      (node (ref "USB2") (pin "D-") (pinfunction "D-_D-") (pintype "bidirectional"))
    )
    (net (code "151") (name "Net-(U6-IO1_2)") (class "Default")
      (node (ref "R46") (pin "1") (pinfunction "1_1") (pintype "passive"))
      (node (ref "U6") (pin "P$6") (pinfunction "IO1_2_P$6") (pintype "bidirectional"))
    )
    (net (code "152") (name "Net-(U6-IO2_1)") (class "Default")
      (node (ref "U6") (pin "P$3") (pinfunction "IO2_1_P$3") (pintype "bidirectional"))
      (node (ref "USB2") (pin "D+") (pinfunction "D+_D+") (pintype "bidirectional"))
    )
    (net (code "153") (name "Net-(U6-IO2_2)") (class "Default")
      (node (ref "R47") (pin "1") (pinfunction "1_1") (pintype "passive"))
      (node (ref "U6") (pin "P$4") (pinfunction "IO2_2_P$4") (pintype "bidirectional"))
    )
    (net (code "154") (name "Net-(U7-Y)") (class "Default")
      (node (ref "R6") (pin "2") (pinfunction "2_2") (pintype "passive"))
      (node (ref "U7") (pin "4") (pinfunction "Y_4") (pintype "bidirectional"))
    )
    (net (code "155") (name "Net-(U8-VBOOT)") (class "Default")
      (node (ref "C48") (pin "2") (pinfunction "2_2") (pintype "passive"))
      (node (ref "D4") (pin "3") (pinfunction "3_3") (pintype "bidirectional"))
      (node (ref "U8") (pin "21") (pinfunction "VBOOT_21") (pintype "bidirectional"))
    )
    (net (code "156") (name "Net-(U8-VCP)") (class "Default")
      (node (ref "C49") (pin "2") (pinfunction "2_2") (pintype "passive"))
      (node (ref "U8") (pin "40") (pinfunction "VCP_40") (pintype "bidirectional"))
    )
    (net (code "157") (name "Net-(U9-VBOOT)") (class "Default")
      (node (ref "C20") (pin "2") (pinfunction "2_2") (pintype "passive"))
      (node (ref "D5") (pin "3") (pinfunction "3_3") (pintype "bidirectional"))
      (node (ref "U9") (pin "21") (pinfunction "VBOOT_21") (pintype "bidirectional"))
    )
    (net (code "158") (name "Net-(U9-VCP)") (class "Default")
      (node (ref "C45") (pin "2") (pinfunction "2_2") (pintype "passive"))
      (node (ref "U9") (pin "40") (pinfunction "VCP_40") (pintype "bidirectional"))
    )
    (net (code "159") (name "Net-(U10A-VCAP_2)") (class "Default")
      (node (ref "C37") (pin "1") (pinfunction "1_1") (pintype "passive"))
      (node (ref "U10") (pin "73") (pinfunction "VCAP_2_73") (pintype "power_in"))
    )
    (net (code "160") (name "Net-(U10B-OSC_IN)") (class "Default")
      (node (ref "C19") (pin "1") (pinfunction "1_1") (pintype "passive"))
      (node (ref "U10") (pin "12") (pinfunction "OSC_IN_12") (pintype "input"))
      (node (ref "Y1") (pin "2") (pinfunction "2_2") (pintype "passive"))
    )
    (net (code "161") (name "Net-(U10B-OSC_OUT)") (class "Default")
      (node (ref "C2") (pin "1") (pinfunction "1_1") (pintype "passive"))
      (node (ref "U10") (pin "13") (pinfunction "OSC_OUT_13") (pintype "output"))
      (node (ref "Y1") (pin "1") (pinfunction "1_1") (pintype "passive"))
    )
    (net (code "162") (name "Net-(U10M-VCAP_1)") (class "Default")
      (node (ref "C7") (pin "1") (pinfunction "1_1") (pintype "passive"))
      (node (ref "U10") (pin "49") (pinfunction "VCAP_1_49") (pintype "power_in"))
    )
    (net (code "163") (name "Net-(U10N-BOOT0)") (class "Default")
      (node (ref "R42") (pin "2") (pinfunction "2_2") (pintype "passive"))
      (node (ref "U10") (pin "94") (pinfunction "BOOT0_94") (pintype "input"))
    )
    (net (code "164") (name "Net-(U11-CAP)") (class "Default")
      (node (ref "C35") (pin "1") (pinfunction "1_1") (pintype "passive"))
      (node (ref "U11") (pin "21") (pinfunction "CAP_21") (pintype "bidirectional"))
    )
    (net (code "165") (name "Net-(U12-QA)") (class "Default")
      (node (ref "LCD") (pin "DB0") (pinfunction "DB0_DB0") (pintype "bidirectional"))
      (node (ref "U12") (pin "3") (pinfunction "QA_3") (pintype "bidirectional"))
    )
    (net (code "166") (name "Net-(U12-QB)") (class "Default")
      (node (ref "LCD") (pin "DB1") (pinfunction "DB1_DB1") (pintype "bidirectional"))
      (node (ref "U12") (pin "4") (pinfunction "QB_4") (pintype "bidirectional"))
    )
    (net (code "167") (name "Net-(U12-QC)") (class "Default")
      (node (ref "LCD") (pin "DB2") (pinfunction "DB2_DB2") (pintype "bidirectional"))
      (node (ref "U12") (pin "5") (pinfunction "QC_5") (pintype "bidirectional"))
    )
    (net (code "168") (name "Net-(U12-QD)") (class "Default")
      (node (ref "LCD") (pin "DB3") (pinfunction "DB3_DB3") (pintype "bidirectional"))
      (node (ref "U12") (pin "6") (pinfunction "QD_6") (pintype "bidirectional"))
    )
    (net (code "169") (name "Net-(U12-QE)") (class "Default")
      (node (ref "LCD") (pin "DB4") (pinfunction "DB4_DB4") (pintype "bidirectional"))
      (node (ref "U12") (pin "10") (pinfunction "QE_10") (pintype "bidirectional"))
    )
    (net (code "170") (name "Net-(U12-QF)") (class "Default")
      (node (ref "LCD") (pin "DB5") (pinfunction "DB5_DB5") (pintype "bidirectional"))
      (node (ref "U12") (pin "11") (pinfunction "QF_11") (pintype "bidirectional"))
    )
    (net (code "171") (name "Net-(U12-QG)") (class "Default")
      (node (ref "LCD") (pin "DB6") (pinfunction "DB6_DB6") (pintype "bidirectional"))
      (node (ref "U12") (pin "12") (pinfunction "QG_12") (pintype "bidirectional"))
    )
    (net (code "172") (name "Net-(U12-QH)") (class "Default")
      (node (ref "LCD") (pin "DB7") (pinfunction "DB7_DB7") (pintype "bidirectional"))
      (node (ref "U12") (pin "13") (pinfunction "QH_13") (pintype "bidirectional"))
    )
    (net (code "173") (name "Net-(XB1-PWM0{slash}RSSI)") (class "Default")
      (node (ref "D11") (pin "A") (pinfunction "A_A") (pintype "passive"))
      (node (ref "XB1") (pin "6") (pinfunction "PWM0/RSSI_6") (pintype "output"))
    )
    (net (code "174") (name "unconnected-(J1-Pad1)") (class "Default")
      (node (ref "J1") (pin "1") (pinfunction "1_1") (pintype "passive"))
    )
    (net (code "175") (name "unconnected-(J1-Pad6)") (class "Default")
      (node (ref "J1") (pin "6") (pinfunction "6_6") (pintype "passive"))
    )
    (net (code "176") (name "unconnected-(U1-LDO3-Pad7)") (class "Default")
      (node (ref "U1") (pin "7") (pinfunction "LDO3_7") (pintype "bidirectional"))
    )
    (net (code "177") (name "unconnected-(U1-PG_3-Pad27)") (class "Default")
      (node (ref "U1") (pin "27") (pinfunction "PG_3_27") (pintype "bidirectional"))
    )
    (net (code "178") (name "unconnected-(U1-PG_5-Pad26)") (class "Default")
      (node (ref "U1") (pin "26") (pinfunction "PG_5_26") (pintype "bidirectional"))
    )
    (net (code "179") (name "unconnected-(U1-PG_LDO3-Pad6)") (class "Default")
      (node (ref "U1") (pin "6") (pinfunction "PG_LDO3_6") (pintype "bidirectional"))
    )
    (net (code "180") (name "unconnected-(U7-NC-Pad1)") (class "Default")
      (node (ref "U7") (pin "1") (pinfunction "NC_1") (pintype "bidirectional"))
    )
    (net (code "181") (name "unconnected-(USB2-PadID)") (class "Default")
      (node (ref "USB2") (pin "ID") (pinfunction "ID_ID") (pintype "bidirectional"))
    )
    (net (code "182") (name "unconnected-(USD-NC-Pad1)") (class "Default")
      (node (ref "USD") (pin "1") (pinfunction "NC_1") (pintype "bidirectional"))
    )
    (net (code "183") (name "unconnected-(USD-RSV-Pad8)") (class "Default")
      (node (ref "USD") (pin "8") (pinfunction "RSV_8") (pintype "bidirectional"))
    )
    (net (code "184") (name "unconnected-(XB1-AD0{slash}DIO0-Pad20)") (class "Default")
      (node (ref "XB1") (pin "20") (pinfunction "AD0/DIO0_20") (pintype "bidirectional"))
    )
    (net (code "185") (name "unconnected-(XB1-AD1{slash}DIO1-Pad19)") (class "Default")
      (node (ref "XB1") (pin "19") (pinfunction "AD1/DIO1_19") (pintype "bidirectional"))
    )
    (net (code "186") (name "unconnected-(XB1-AD2{slash}DIO2-Pad18)") (class "Default")
      (node (ref "XB1") (pin "18") (pinfunction "AD2/DIO2_18") (pintype "bidirectional"))
    )
    (net (code "187") (name "unconnected-(XB1-ASSOC{slash}AD5{slash}DIO5-Pad15)") (class "Default")
      (node (ref "XB1") (pin "15") (pinfunction "ASSOC/AD5/DIO5_15") (pintype "bidirectional"))
    )
    (net (code "188") (name "unconnected-(XB1-CD{slash}DOUT_EN{slash}DO8-Pad4)") (class "Default")
      (node (ref "XB1") (pin "4") (pinfunction "CD/DOUT_EN/DO8_4") (pintype "output"))
    )
    (net (code "189") (name "unconnected-(XB1-COORD_SEL{slash}AD3{slash}DIO3-Pad17)") (class "Default")
      (node (ref "XB1") (pin "17") (pinfunction "COORD_SEL/AD3/DIO3_17") (pintype "bidirectional"))
    )
    (net (code "190") (name "unconnected-(XB1-ON{slash}~{SLEEP}-Pad13)") (class "Default")
      (node (ref "XB1") (pin "13") (pinfunction "ON/~{SLEEP}_13") (pintype "output"))
    )
    (net (code "191") (name "unconnected-(XB1-RF_TX{slash}AD4{slash}DIO4-Pad11)") (class "Default")
      (node (ref "XB1") (pin "11") (pinfunction "RF_TX/AD4/DIO4_11") (pintype "bidirectional"))
    )
    (net (code "192") (name "unconnected-(XB1-VREF-Pad14)") (class "Default")
      (node (ref "XB1") (pin "14") (pinfunction "VREF_14") (pintype "input"))
    )
    (net (code "193") (name "unconnected-(XB1-~{CTS}{slash}DIO7-Pad12)") (class "Default")
      (node (ref "XB1") (pin "12") (pinfunction "~{CTS}/DIO7_12") (pintype "bidirectional"))
    )
    (net (code "194") (name "unconnected-(XB1-~{DTR}{slash}SLEEP_RQ{slash}DI8-Pad9)") (class "Default")
      (node (ref "XB1") (pin "9") (pinfunction "~{DTR}/SLEEP_RQ/DI8_9") (pintype "bidirectional"))
    )
    (net (code "195") (name "unconnected-(XB1-~{RESET}-Pad5)") (class "Default")
      (node (ref "XB1") (pin "5") (pinfunction "~{RESET}_5") (pintype "input"))
    )
    (net (code "196") (name "unconnected-(XB1-~{RTS}{slash}AD6{slash}DIO6-Pad16)") (class "Default")
      (node (ref "XB1") (pin "16") (pinfunction "~{RTS}/AD6/DIO6_16") (pintype "bidirectional"))
    )
  )
)
